# Mixer_NEXT_GEN_V3_2026-02-06.net
KiCad netlist of a schematic drawn in EasyEDA Pro
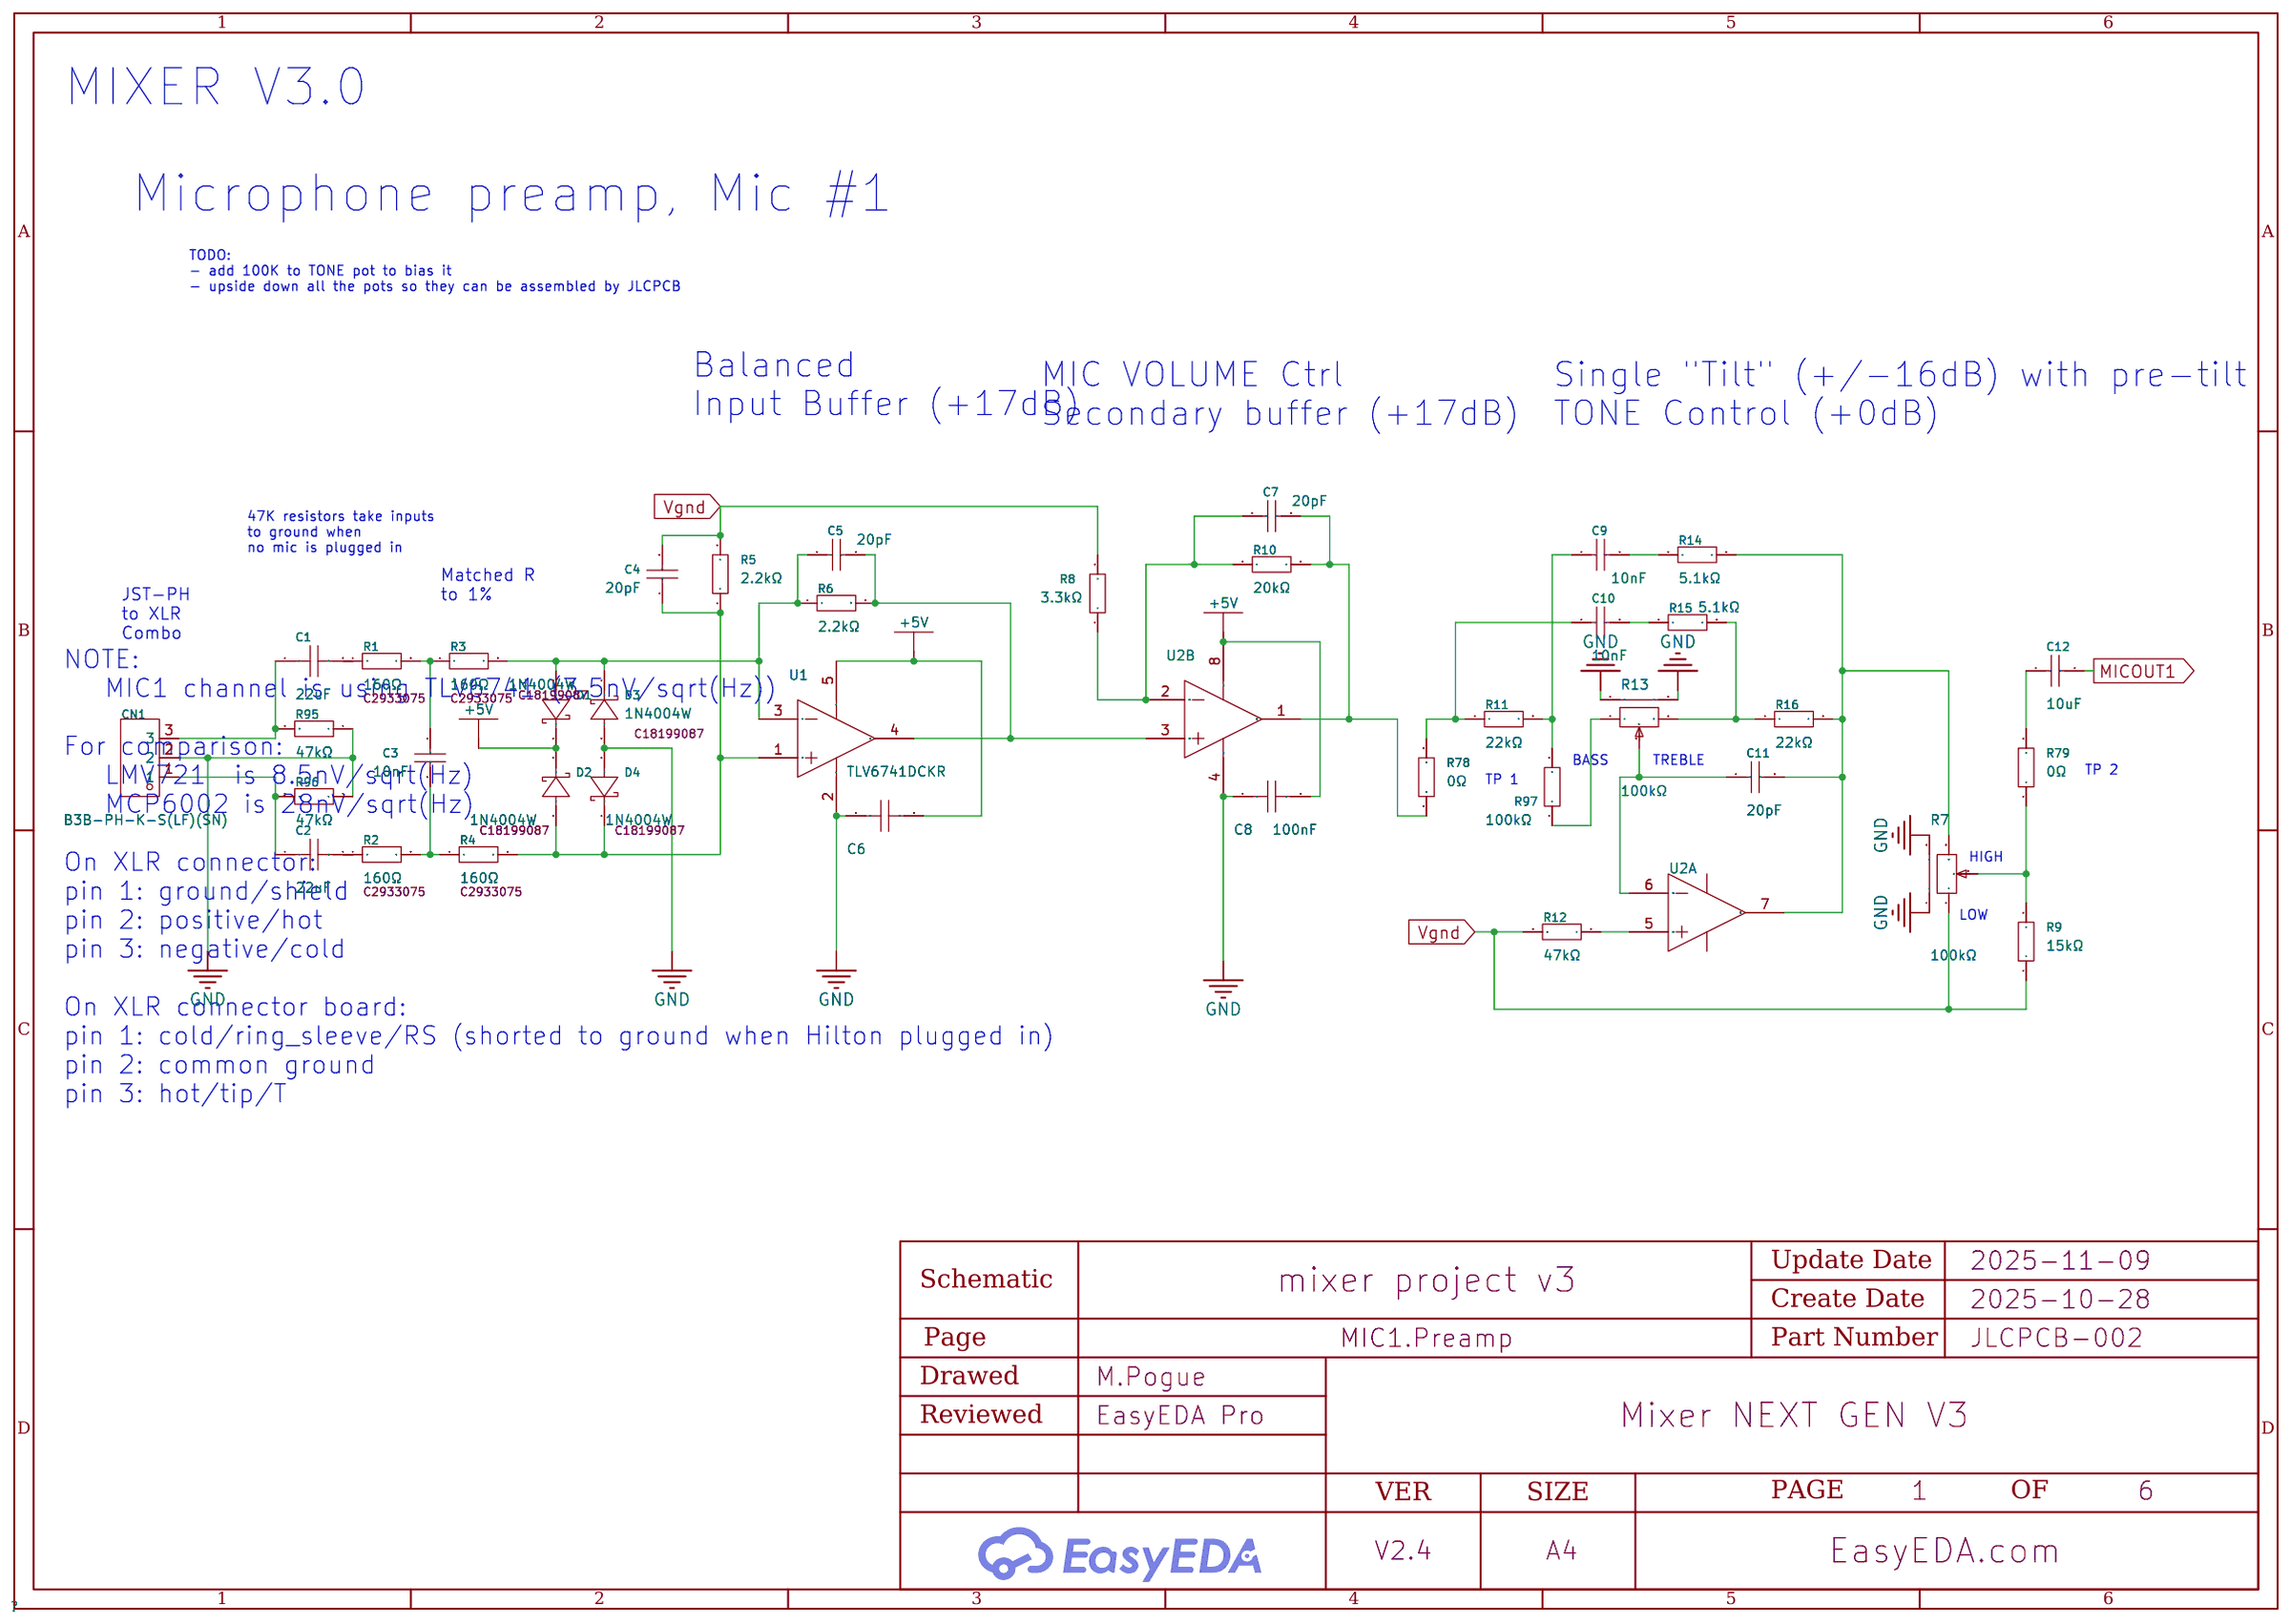
[diagram p0: MIC1.Preamp]
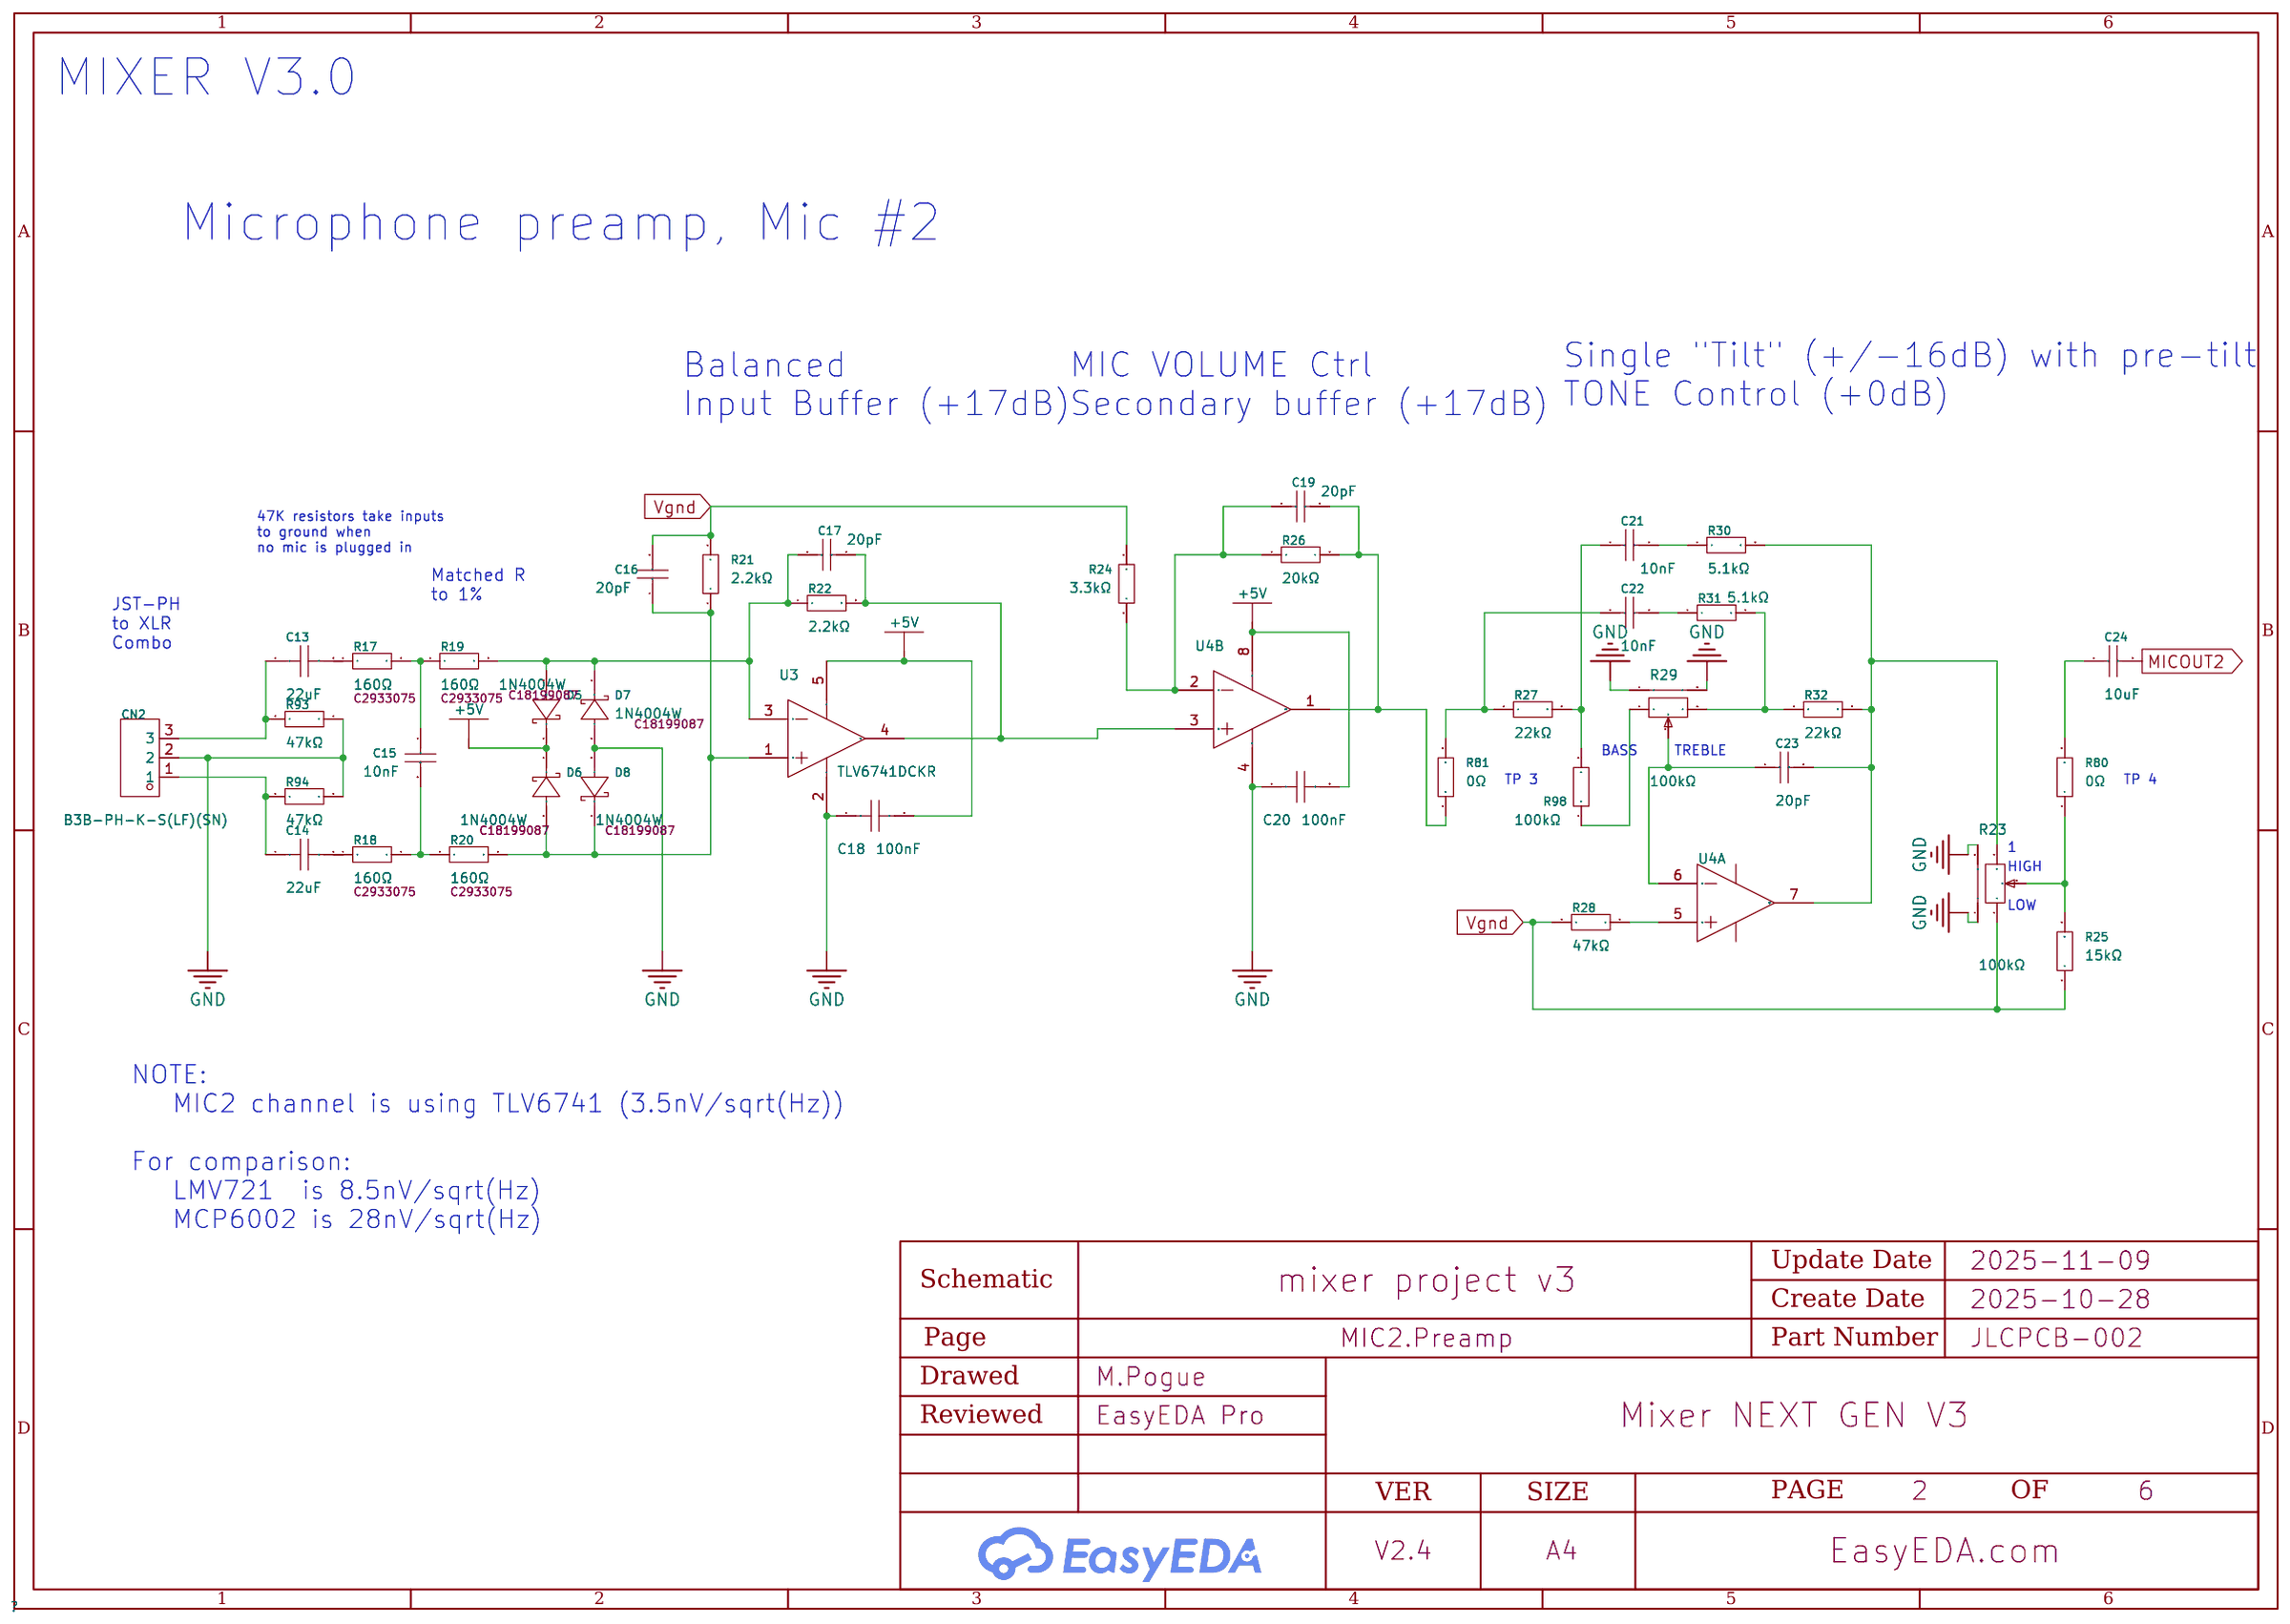
[diagram p1: MIC2.Preamp]
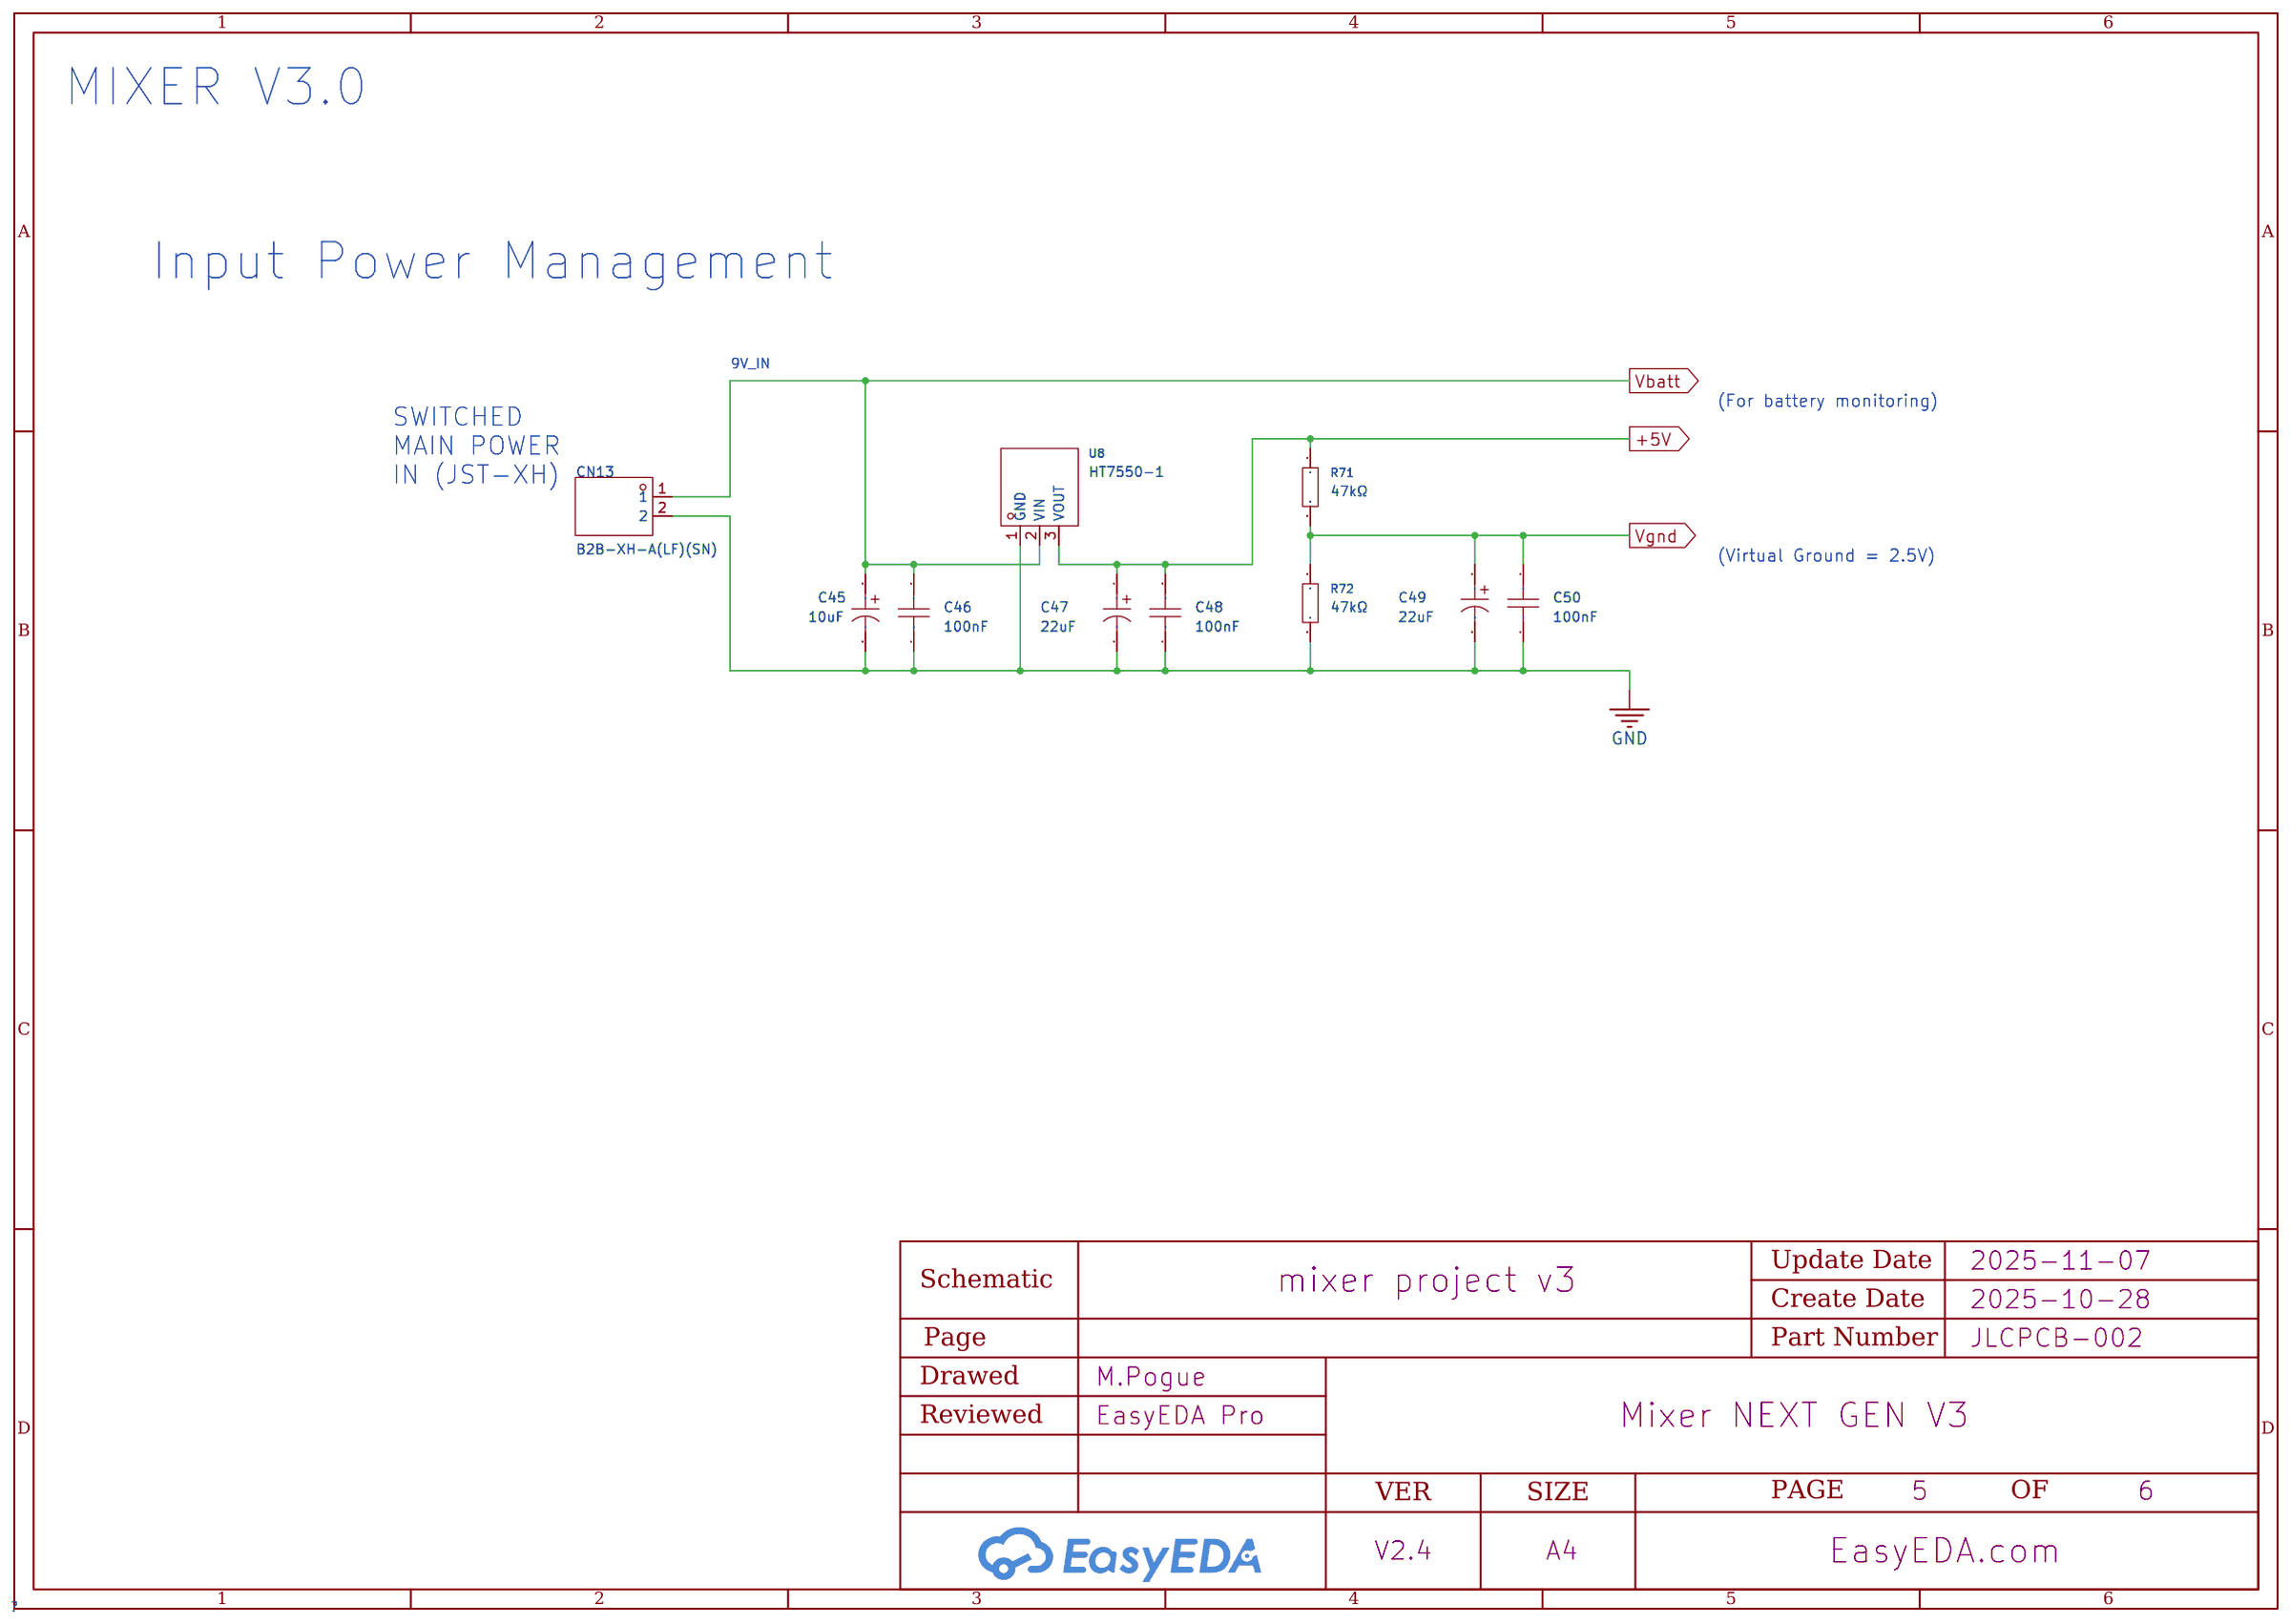
[diagram p2: PowerSupply]
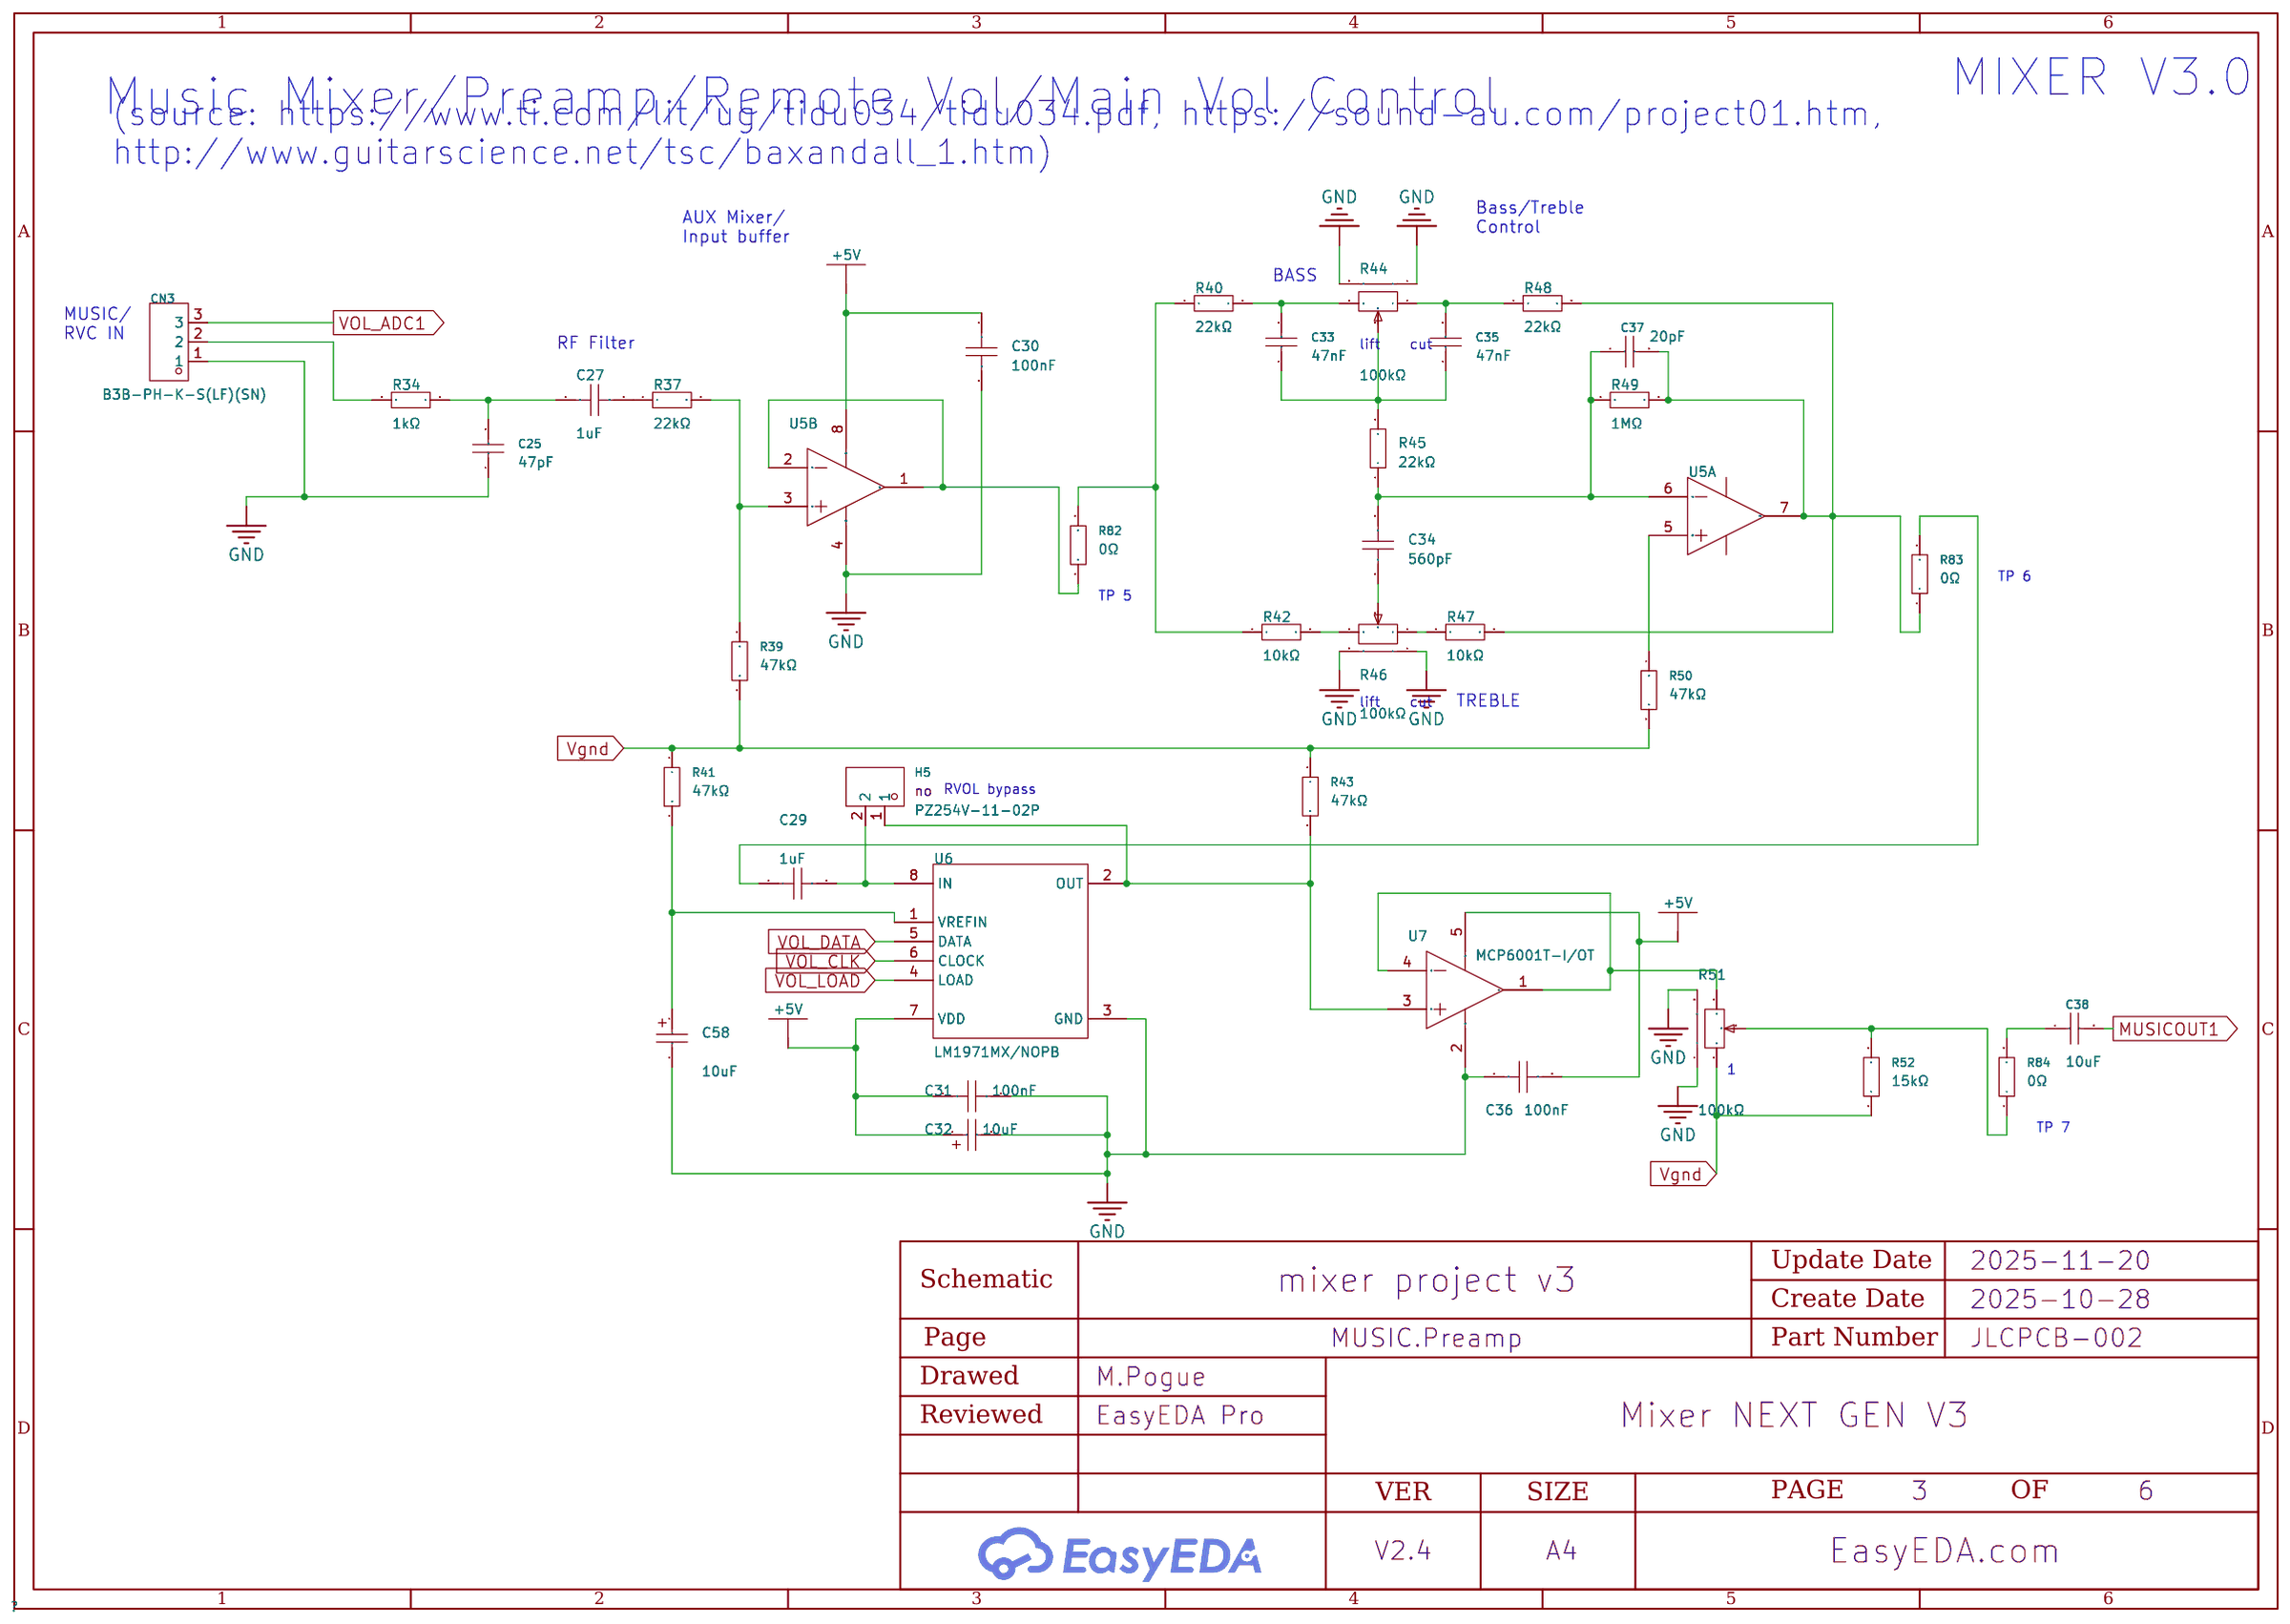
[diagram p3: MUSIC.Preamp]
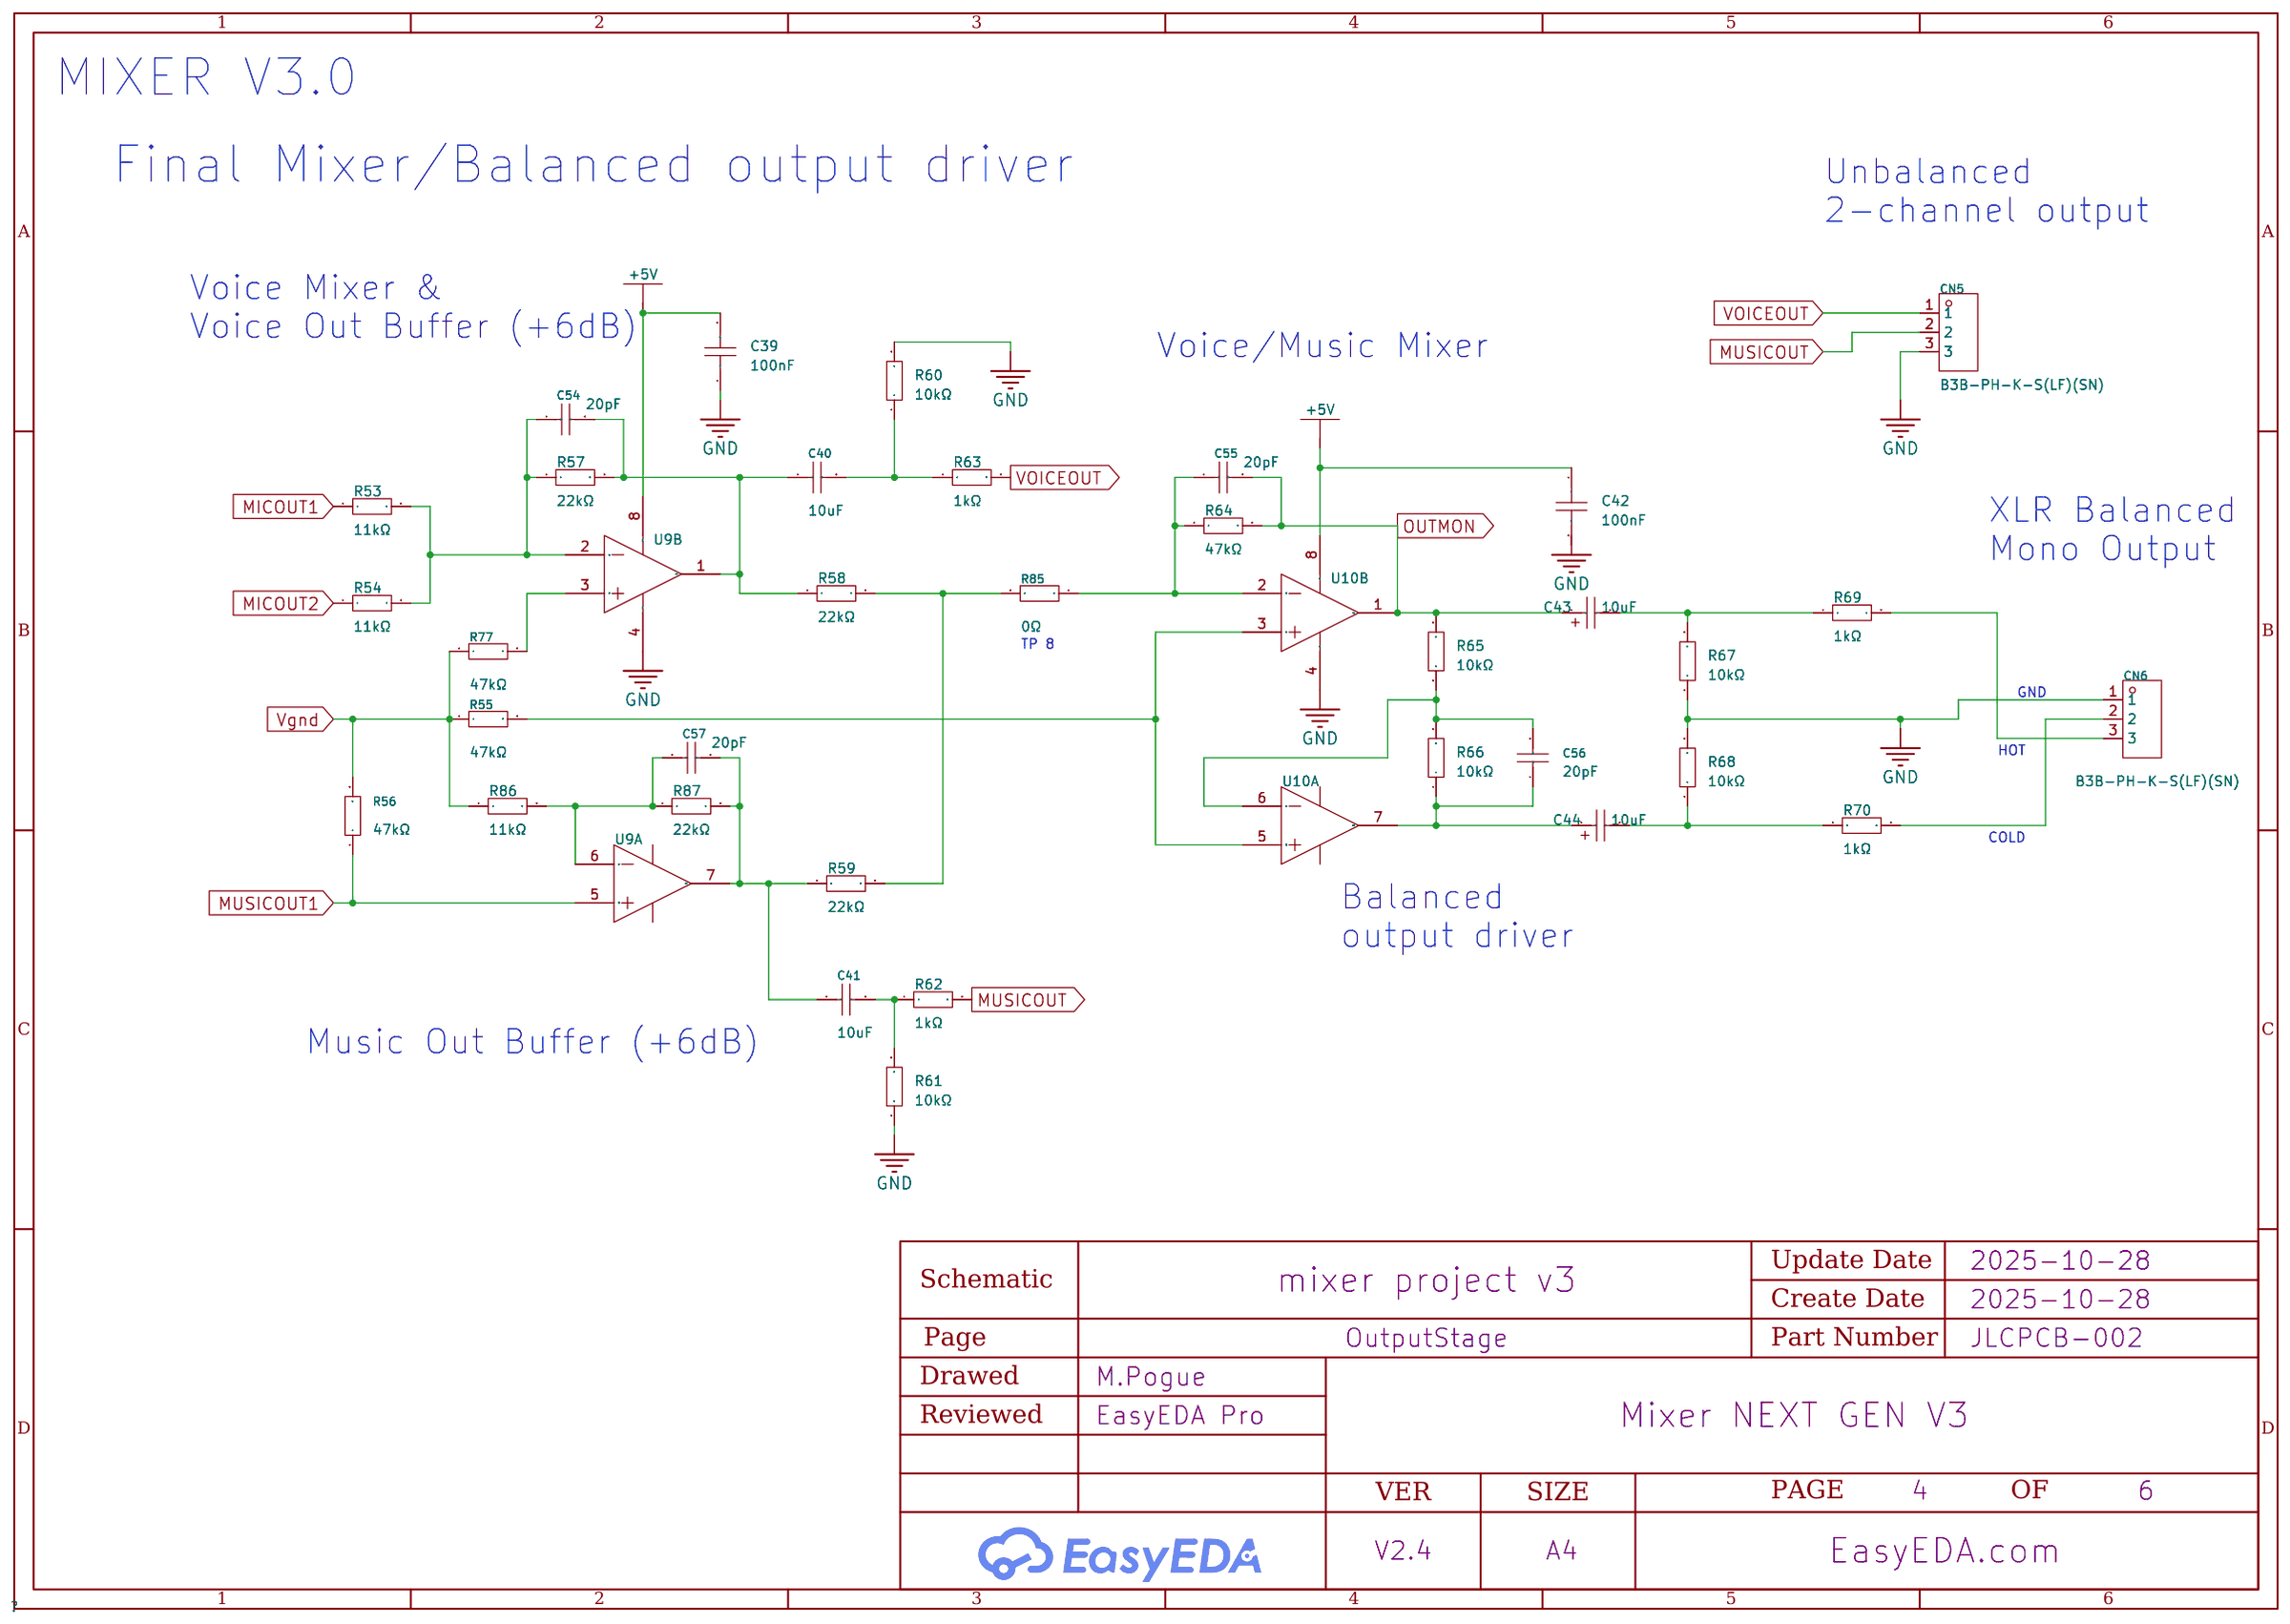
[diagram p4: OutputStage]
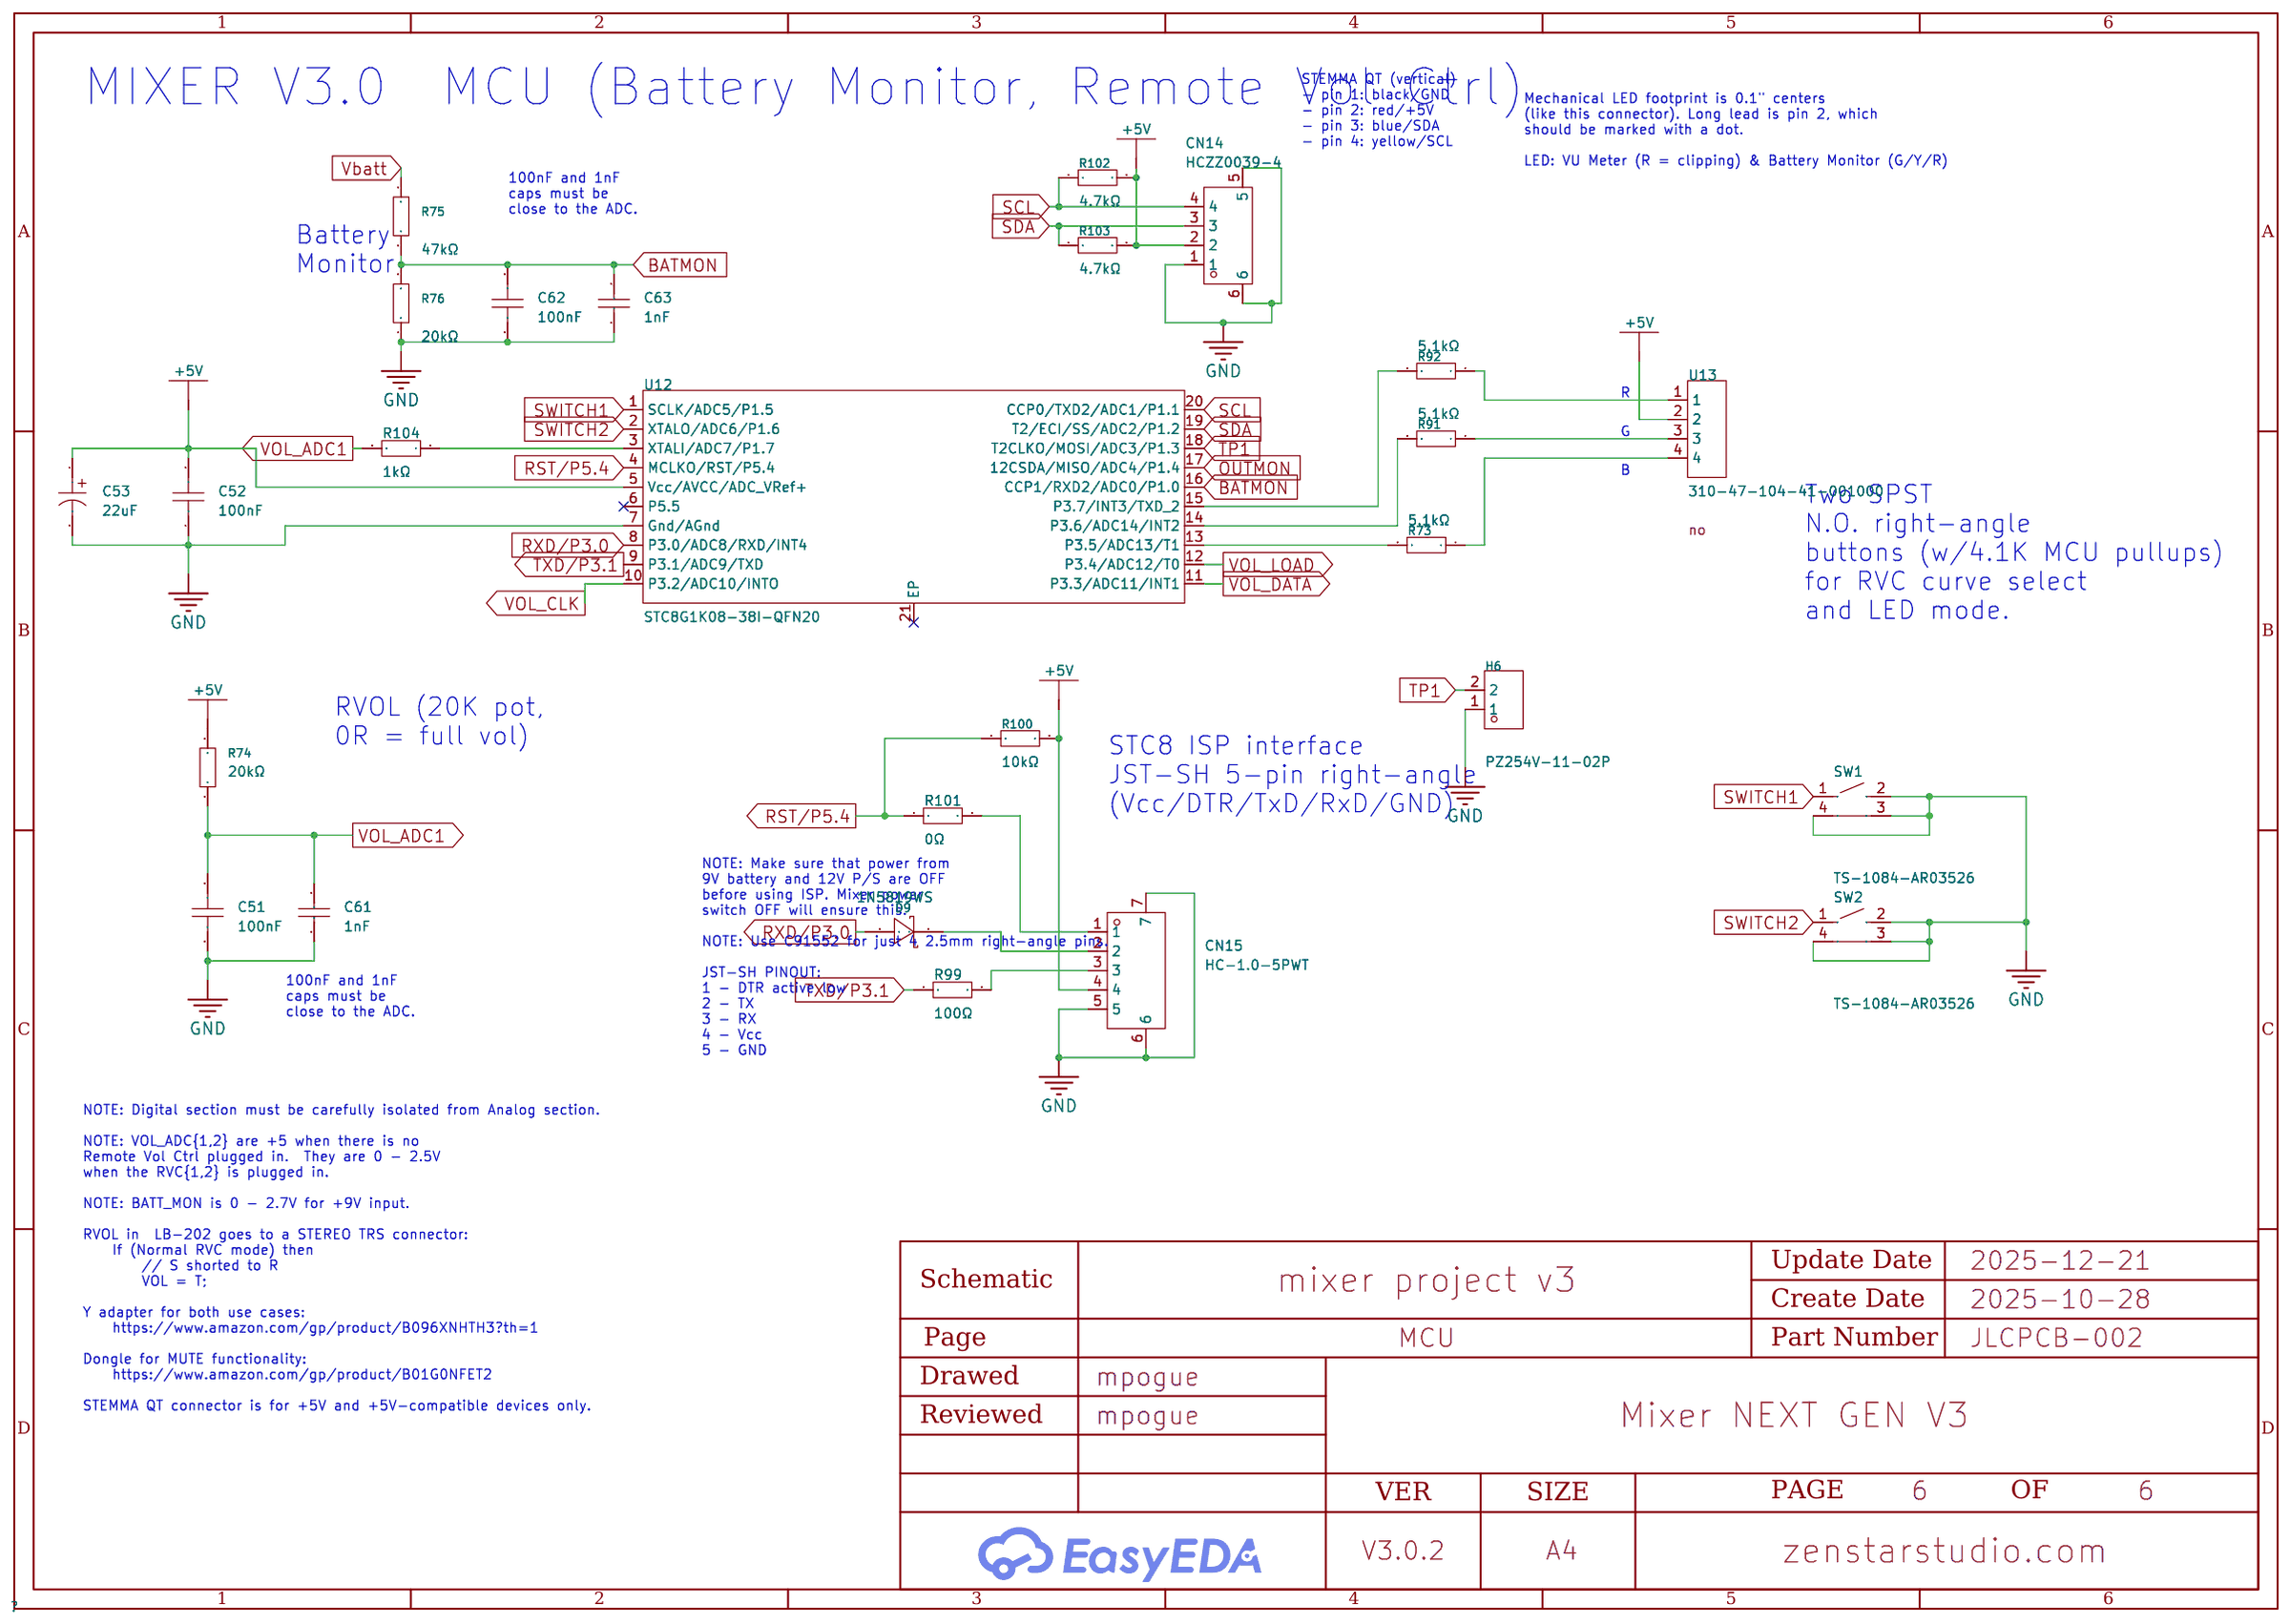
[diagram p5: MCU]

(export (version "E")
  (design (tool "Eeschema 10.0.6"))
  (components
    (comp (ref "C1")
      (value "22uF")
      (footprint "easyedapro:C0805")
      (fields
        (field (name "Manufacturer Part") "CL21A226MAQNNNE")
        (field (name "Manufacturer") "SAMSUNG(三星)")
      )
      (libsource (lib "easyedapro") (part "CL21A226MAQNNNE"))
    )
    (comp (ref "C2")
      (value "22uF")
      (footprint "easyedapro:C0805")
      (fields
        (field (name "Manufacturer Part") "CL21A226MAQNNNE")
        (field (name "Manufacturer") "SAMSUNG(三星)")
      )
      (libsource (lib "easyedapro") (part "CL21A226MAQNNNE"))
    )
    (comp (ref "C3")
      (value "10nF")
      (footprint "easyedapro:C0402")
      (fields
        (field (name "Manufacturer Part") "CL05B103KB5NNNC")
        (field (name "Manufacturer") "SAMSUNG(三星)")
      )
      (libsource (lib "easyedapro") (part "CL05B103KB5NNNC"))
    )
    (comp (ref "C4")
      (value "20pF")
      (footprint "easyedapro:C0402")
      (fields (field (name "Manufacturer Part") "0402CG200J500NT") (field (name "Manufacturer") "FH(风华)"))
      (libsource (lib "easyedapro") (part "0402CG200J500NT"))
    )
    (comp (ref "C5")
      (value "20pF")
      (footprint "easyedapro:C0402")
      (fields (field (name "Manufacturer Part") "0402CG200J500NT") (field (name "Manufacturer") "FH(风华)"))
      (libsource (lib "easyedapro") (part "0402CG200J500NT"))
    )
    (comp (ref "C6")
      (value "100nF")
      (fields
        (field (name "Manufacturer Part") "CL05B104KO5NNNC")
        (field (name "Manufacturer") "SAMSUNG(三星)")
      )
      (libsource (lib "easyedapro") (part "CAP"))
    )
    (comp (ref "C7")
      (value "20pF")
      (footprint "easyedapro:C0402")
      (fields (field (name "Manufacturer Part") "0402CG200J500NT") (field (name "Manufacturer") "FH(风华)"))
      (libsource (lib "easyedapro") (part "0402CG200J500NT"))
    )
    (comp (ref "C8")
      (value "100nF")
      (fields
        (field (name "Manufacturer Part") "CL05B104KO5NNNC")
        (field (name "Manufacturer") "SAMSUNG(三星)")
      )
      (libsource (lib "easyedapro") (part "CAP"))
    )
    (comp (ref "C9")
      (value "10nF")
      (fields
        (field (name "Manufacturer Part") "CL05B103KB5NNNC")
        (field (name "Manufacturer") "SAMSUNG(三星)")
      )
      (libsource (lib "easyedapro") (part "0402B472K500NT"))
    )
    (comp (ref "C10")
      (value "10nF")
      (fields
        (field (name "Manufacturer Part") "CL05B103KB5NNNC")
        (field (name "Manufacturer") "SAMSUNG(三星)")
      )
      (libsource (lib "easyedapro") (part "0402B472K500NT"))
    )
    (comp (ref "C11")
      (value "20pF")
      (footprint "easyedapro:C0402")
      (fields (field (name "Manufacturer Part") "0402CG200J500NT") (field (name "Manufacturer") "FH(风华)"))
      (libsource (lib "easyedapro") (part "0402CG200J500NT"))
    )
    (comp (ref "C12")
      (value "10uF")
      (footprint "easyedapro:C1206")
      (fields
        (field (name "Manufacturer Part") "CL31A106KBHNNNE")
        (field (name "Manufacturer") "SAMSUNG(三星)")
      )
      (libsource (lib "easyedapro") (part "CL31A106KBHNNNE"))
    )
    (comp (ref "CN1")
      (value "B3B-PH-K-S(LF)(SN)")
      (footprint "easyedapro:CONN-TH_B3B-PH-K-S")
      (fields (field (name "Manufacturer") "JST"))
      (libsource (lib "easyedapro") (part "B3B-PH-K-S(LF)(SN)"))
    )
    (comp (ref "D1")
      (value "1N4004W")
      (footprint "easyedapro:SOD-123FL_L2.7-W1.8-LS3.8-RD")
      (fields (field (name "Manufacturer") "R+O(宏嘉诚)") (field (name "Supplier Part") "C18199087"))
      (libsource (lib "easyedapro") (part "1N4004W_C18199087"))
    )
    (comp (ref "D2")
      (value "1N4004W")
      (footprint "easyedapro:SOD-123FL_L2.7-W1.8-LS3.8-RD")
      (fields (field (name "Manufacturer") "R+O(宏嘉诚)") (field (name "Supplier Part") "C18199087"))
      (libsource (lib "easyedapro") (part "1N4004W_C18199087"))
    )
    (comp (ref "D3")
      (value "1N4004W")
      (footprint "easyedapro:SOD-123FL_L2.7-W1.8-LS3.8-RD")
      (fields (field (name "Manufacturer") "R+O(宏嘉诚)") (field (name "Supplier Part") "C18199087"))
      (libsource (lib "easyedapro") (part "1N4004W_C18199087"))
    )
    (comp (ref "D4")
      (value "1N4004W")
      (footprint "easyedapro:SOD-123FL_L2.7-W1.8-LS3.8-RD")
      (fields (field (name "Manufacturer") "R+O(宏嘉诚)") (field (name "Supplier Part") "C18199087"))
      (libsource (lib "easyedapro") (part "1N4004W_C18199087"))
    )
    (comp (ref "R1")
      (value "160Ω")
      (footprint "easyedapro:R0402")
      (fields
        (field (name "Manufacturer Part") "FRC0402F1600TS")
        (field (name "Manufacturer") "FOJAN(富捷)")
        (field (name "Supplier Part") "C2933075")
      )
      (libsource (lib "easyedapro") (part "RC-02W1600FT"))
    )
    (comp (ref "R2")
      (value "160Ω")
      (footprint "easyedapro:R0402")
      (fields
        (field (name "Manufacturer Part") "FRC0402F1600TS")
        (field (name "Manufacturer") "FOJAN(富捷)")
        (field (name "Supplier Part") "C2933075")
      )
      (libsource (lib "easyedapro") (part "RC-02W1600FT"))
    )
    (comp (ref "R3")
      (value "160Ω")
      (footprint "easyedapro:R0402")
      (fields
        (field (name "Manufacturer Part") "FRC0402F1600TS")
        (field (name "Manufacturer") "FOJAN(富捷)")
        (field (name "Supplier Part") "C2933075")
      )
      (libsource (lib "easyedapro") (part "RC-02W1600FT"))
    )
    (comp (ref "R4")
      (value "160Ω")
      (footprint "easyedapro:R0402")
      (fields
        (field (name "Manufacturer Part") "FRC0402F1600TS")
        (field (name "Manufacturer") "FOJAN(富捷)")
        (field (name "Supplier Part") "C2933075")
      )
      (libsource (lib "easyedapro") (part "RC-02W1600FT"))
    )
    (comp (ref "R5")
      (value "2.2kΩ")
      (footprint "easyedapro:R0402")
      (fields
        (field (name "Manufacturer Part") "0402WGF2201TCE")
        (field (name "Manufacturer") "UNI-ROYAL(厚声)")
      )
      (libsource (lib "easyedapro") (part "0402WGF2201TCE"))
    )
    (comp (ref "R6")
      (value "2.2kΩ")
      (footprint "easyedapro:R0402")
      (fields
        (field (name "Manufacturer Part") "0402WGF2201TCE")
        (field (name "Manufacturer") "UNI-ROYAL(厚声)")
      )
      (libsource (lib "easyedapro") (part "0402WGF2201TCE"))
    )
    (comp (ref "R7")
      (value "100kΩ")
      (footprint "easyedapro:RES-ADJ-TH_RK09K1130AJ3")
      (description "Resistance: Tolerance:±20% Tolerance:±20% Power(Watts):50mW Turns:- Rated Voltage:20V")
      (fields
        (field (name "Manufacturer Part") "RK09K1130AU2")
        (field (name "Manufacturer") "ALPSALPINE(阿尔卑斯阿尔派)")
      )
      (libsource (lib "easyedapro") (part "RK09K1130AU2"))
    )
    (comp (ref "R8")
      (value "3.3kΩ")
      (footprint "easyedapro:R0402")
      (fields
        (field (name "Manufacturer Part") "0402WGF3301TCE")
        (field (name "Manufacturer") "UNI-ROYAL(厚声)")
      )
      (libsource (lib "easyedapro") (part "0402WGF3301TCE"))
    )
    (comp (ref "R9")
      (value "15kΩ")
      (footprint "easyedapro:R0402")
      (fields
        (field (name "Manufacturer Part") "0402WGF1502TCE")
        (field (name "Manufacturer") "UNI-ROYAL(厚声)")
      )
      (libsource (lib "easyedapro") (part "0402WGF1502TCE"))
    )
    (comp (ref "R10")
      (value "20kΩ")
      (footprint "easyedapro:R0402")
      (fields
        (field (name "Manufacturer Part") "0402WGF2002TCE")
        (field (name "Manufacturer") "UNI-ROYAL(厚声)")
      )
      (libsource (lib "easyedapro") (part "0402WGF2002TCE"))
    )
    (comp (ref "R11")
      (value "22kΩ")
      (footprint "easyedapro:R0402")
      (fields
        (field (name "Manufacturer Part") "0402WGF2202TCE")
        (field (name "Manufacturer") "UNI-ROYAL(厚声)")
      )
      (libsource (lib "easyedapro") (part "0402WGF2202TCE"))
    )
    (comp (ref "R12")
      (value "47kΩ")
      (footprint "easyedapro:R0402")
      (fields
        (field (name "Manufacturer Part") "0402WGF4702TCE")
        (field (name "Manufacturer") "UNI-ROYAL(厚声)")
      )
      (libsource (lib "easyedapro") (part "0402WGF4702TCE"))
    )
    (comp (ref "R13")
      (value "100kΩ")
      (footprint "easyedapro:RES-ADJ-TH_RK09K1130AJ3")
      (description "Resistance: Tolerance:±20% Tolerance:±20% Power(Watts):50mW Turns:- Rated Voltage:20V")
      (fields
        (field (name "Manufacturer Part") "RK09K1130AU2")
        (field (name "Manufacturer") "ALPSALPINE(阿尔卑斯阿尔派)")
      )
      (libsource (lib "easyedapro") (part "RK09K1130AU2"))
    )
    (comp (ref "R14")
      (value "5.1kΩ")
      (footprint "easyedapro:R0402")
      (fields
        (field (name "Manufacturer Part") "0402WGF5101TCE")
        (field (name "Manufacturer") "UNI-ROYAL(厚声)")
      )
      (libsource (lib "easyedapro") (part "0402WGF5101TCE"))
    )
    (comp (ref "R15")
      (value "5.1kΩ")
      (footprint "easyedapro:R0402")
      (fields
        (field (name "Manufacturer Part") "0402WGF5101TCE")
        (field (name "Manufacturer") "UNI-ROYAL(厚声)")
      )
      (libsource (lib "easyedapro") (part "0402WGF5101TCE"))
    )
    (comp (ref "R16")
      (value "22kΩ")
      (footprint "easyedapro:R0402")
      (fields
        (field (name "Manufacturer Part") "0402WGF2202TCE")
        (field (name "Manufacturer") "UNI-ROYAL(厚声)")
      )
      (libsource (lib "easyedapro") (part "0402WGF2202TCE"))
    )
    (comp (ref "R78")
      (value "0Ω")
      (footprint "easyedapro:R0805")
      (fields
        (field (name "Manufacturer Part") "0805W8F0000T5E")
        (field (name "Manufacturer") "UNI-ROYAL(厚声)")
      )
      (libsource (lib "easyedapro") (part "0805W8F0000T5E"))
    )
    (comp (ref "R79")
      (value "0Ω")
      (footprint "easyedapro:R0805")
      (fields
        (field (name "Manufacturer Part") "0805W8F0000T5E")
        (field (name "Manufacturer") "UNI-ROYAL(厚声)")
      )
      (libsource (lib "easyedapro") (part "0805W8F0000T5E"))
    )
    (comp (ref "R95")
      (value "47kΩ")
      (footprint "easyedapro:R0402")
      (fields
        (field (name "Manufacturer Part") "0402WGF4702TCE")
        (field (name "Manufacturer") "UNI-ROYAL(厚声)")
      )
      (libsource (lib "easyedapro") (part "0402WGF4702TCE"))
    )
    (comp (ref "R96")
      (value "47kΩ")
      (footprint "easyedapro:R0402")
      (fields
        (field (name "Manufacturer Part") "0402WGF4702TCE")
        (field (name "Manufacturer") "UNI-ROYAL(厚声)")
      )
      (libsource (lib "easyedapro") (part "0402WGF4702TCE"))
    )
    (comp (ref "R97")
      (value "100kΩ")
      (footprint "easyedapro:R0402")
      (fields
        (field (name "Manufacturer Part") "0402WGF1003TCE")
        (field (name "Manufacturer") "UNI-ROYAL(厚声)")
      )
      (libsource (lib "easyedapro") (part "0402WGF1003TCE"))
    )
    (comp (ref "U1")
      (value "TLV6741DCKR")
      (footprint "easyedapro:SC-70-5_L2.0-W1.3-P0.65-LS2.1-BR")
      (fields (field (name "Manufacturer") "TI(德州仪器)"))
      (libsource (lib "easyedapro") (part "TLV6741DCKR"))
    )
    (comp (ref "U2")
      (value "MCP6002-I/SN")
      (footprint "easyedapro:SOIC-8_L4.9-W3.9-P1.27-LS6.0-BL")
      (fields (field (name "Manufacturer") "MICROCHIP(美国微芯)"))
      (libsource (lib "easyedapro") (part "MCP6002-I/SN"))
    )
    (comp (ref "C13")
      (value "22uF")
      (footprint "easyedapro:C0805")
      (fields
        (field (name "Manufacturer Part") "CL21A226MAQNNNE")
        (field (name "Manufacturer") "SAMSUNG(三星)")
      )
      (libsource (lib "easyedapro") (part "CL21A226MAQNNNE"))
    )
    (comp (ref "C14")
      (value "22uF")
      (footprint "easyedapro:C0805")
      (fields
        (field (name "Manufacturer Part") "CL21A226MAQNNNE")
        (field (name "Manufacturer") "SAMSUNG(三星)")
      )
      (libsource (lib "easyedapro") (part "CL21A226MAQNNNE"))
    )
    (comp (ref "C15")
      (value "10nF")
      (footprint "easyedapro:C0402")
      (fields
        (field (name "Manufacturer Part") "CL05B103KB5NNNC")
        (field (name "Manufacturer") "SAMSUNG(三星)")
      )
      (libsource (lib "easyedapro") (part "CL05B103KB5NNNC"))
    )
    (comp (ref "C16")
      (value "20pF")
      (footprint "easyedapro:C0402")
      (fields (field (name "Manufacturer Part") "0402CG200J500NT") (field (name "Manufacturer") "FH(风华)"))
      (libsource (lib "easyedapro") (part "0402CG200J500NT"))
    )
    (comp (ref "C17")
      (value "20pF")
      (footprint "easyedapro:C0402")
      (fields (field (name "Manufacturer Part") "0402CG200J500NT") (field (name "Manufacturer") "FH(风华)"))
      (libsource (lib "easyedapro") (part "0402CG200J500NT"))
    )
    (comp (ref "C18")
      (value "100nF")
      (fields
        (field (name "Manufacturer Part") "CL05B104KO5NNNC")
        (field (name "Manufacturer") "SAMSUNG(三星)")
      )
      (libsource (lib "easyedapro") (part "CAP"))
    )
    (comp (ref "C19")
      (value "20pF")
      (footprint "easyedapro:C0402")
      (fields (field (name "Manufacturer Part") "0402CG200J500NT") (field (name "Manufacturer") "FH(风华)"))
      (libsource (lib "easyedapro") (part "0402CG200J500NT"))
    )
    (comp (ref "C20")
      (value "100nF")
      (fields
        (field (name "Manufacturer Part") "CL05B104KO5NNNC")
        (field (name "Manufacturer") "SAMSUNG(三星)")
      )
      (libsource (lib "easyedapro") (part "CAP"))
    )
    (comp (ref "C21")
      (value "10nF")
      (fields
        (field (name "Manufacturer Part") "CL05B103KB5NNNC")
        (field (name "Manufacturer") "SAMSUNG(三星)")
      )
      (libsource (lib "easyedapro") (part "0402B472K500NT"))
    )
    (comp (ref "C22")
      (value "10nF")
      (fields
        (field (name "Manufacturer Part") "CL05B103KB5NNNC")
        (field (name "Manufacturer") "SAMSUNG(三星)")
      )
      (libsource (lib "easyedapro") (part "0402B472K500NT"))
    )
    (comp (ref "C23")
      (value "20pF")
      (footprint "easyedapro:C0402")
      (fields (field (name "Manufacturer Part") "0402CG200J500NT") (field (name "Manufacturer") "FH(风华)"))
      (libsource (lib "easyedapro") (part "0402CG200J500NT"))
    )
    (comp (ref "C24")
      (value "10uF")
      (footprint "easyedapro:C1206")
      (fields
        (field (name "Manufacturer Part") "CL31A106KBHNNNE")
        (field (name "Manufacturer") "SAMSUNG(三星)")
      )
      (libsource (lib "easyedapro") (part "CL31A106KBHNNNE"))
    )
    (comp (ref "CN2")
      (value "B3B-PH-K-S(LF)(SN)")
      (footprint "easyedapro:CONN-TH_B3B-PH-K-S")
      (fields (field (name "Manufacturer") "JST"))
      (libsource (lib "easyedapro") (part "B3B-PH-K-S(LF)(SN)"))
    )
    (comp (ref "D5")
      (value "1N4004W")
      (footprint "easyedapro:SOD-123FL_L2.7-W1.8-LS3.8-RD")
      (fields (field (name "Manufacturer") "R+O(宏嘉诚)") (field (name "Supplier Part") "C18199087"))
      (libsource (lib "easyedapro") (part "1N4004W_C18199087"))
    )
    (comp (ref "D6")
      (value "1N4004W")
      (footprint "easyedapro:SOD-123FL_L2.7-W1.8-LS3.8-RD")
      (fields (field (name "Manufacturer") "R+O(宏嘉诚)") (field (name "Supplier Part") "C18199087"))
      (libsource (lib "easyedapro") (part "1N4004W_C18199087"))
    )
    (comp (ref "D7")
      (value "1N4004W")
      (footprint "easyedapro:SOD-123FL_L2.7-W1.8-LS3.8-RD")
      (fields (field (name "Manufacturer") "R+O(宏嘉诚)") (field (name "Supplier Part") "C18199087"))
      (libsource (lib "easyedapro") (part "1N4004W_C18199087"))
    )
    (comp (ref "D8")
      (value "1N4004W")
      (footprint "easyedapro:SOD-123FL_L2.7-W1.8-LS3.8-RD")
      (fields (field (name "Manufacturer") "R+O(宏嘉诚)") (field (name "Supplier Part") "C18199087"))
      (libsource (lib "easyedapro") (part "1N4004W_C18199087"))
    )
    (comp (ref "R17")
      (value "160Ω")
      (footprint "easyedapro:R0402")
      (fields
        (field (name "Manufacturer Part") "FRC0402F1600TS")
        (field (name "Manufacturer") "FOJAN(富捷)")
        (field (name "Supplier Part") "C2933075")
      )
      (libsource (lib "easyedapro") (part "RC-02W1600FT"))
    )
    (comp (ref "R18")
      (value "160Ω")
      (footprint "easyedapro:R0402")
      (fields
        (field (name "Manufacturer Part") "FRC0402F1600TS")
        (field (name "Manufacturer") "FOJAN(富捷)")
        (field (name "Supplier Part") "C2933075")
      )
      (libsource (lib "easyedapro") (part "RC-02W1600FT"))
    )
    (comp (ref "R19")
      (value "160Ω")
      (footprint "easyedapro:R0402")
      (fields
        (field (name "Manufacturer Part") "FRC0402F1600TS")
        (field (name "Manufacturer") "FOJAN(富捷)")
        (field (name "Supplier Part") "C2933075")
      )
      (libsource (lib "easyedapro") (part "RC-02W1600FT"))
    )
    (comp (ref "R20")
      (value "160Ω")
      (footprint "easyedapro:R0402")
      (fields
        (field (name "Manufacturer Part") "FRC0402F1600TS")
        (field (name "Manufacturer") "FOJAN(富捷)")
        (field (name "Supplier Part") "C2933075")
      )
      (libsource (lib "easyedapro") (part "RC-02W1600FT"))
    )
    (comp (ref "R21")
      (value "2.2kΩ")
      (footprint "easyedapro:R0402")
      (fields
        (field (name "Manufacturer Part") "0402WGF2201TCE")
        (field (name "Manufacturer") "UNI-ROYAL(厚声)")
      )
      (libsource (lib "easyedapro") (part "0402WGF2201TCE"))
    )
    (comp (ref "R22")
      (value "2.2kΩ")
      (footprint "easyedapro:R0402")
      (fields
        (field (name "Manufacturer Part") "0402WGF2201TCE")
        (field (name "Manufacturer") "UNI-ROYAL(厚声)")
      )
      (libsource (lib "easyedapro") (part "0402WGF2201TCE"))
    )
    (comp (ref "R23")
      (value "100kΩ")
      (footprint "easyedapro:RES-ADJ-TH_RK09K1130AJ3")
      (description "Resistance: Tolerance:±20% Tolerance:±20% Power(Watts):50mW Turns:- Rated Voltage:20V")
      (fields
        (field (name "Manufacturer Part") "RK09K1130AU2")
        (field (name "Manufacturer") "ALPSALPINE(阿尔卑斯阿尔派)")
      )
      (libsource (lib "easyedapro") (part "RK09K1130AU2"))
    )
    (comp (ref "R24")
      (value "3.3kΩ")
      (footprint "easyedapro:R0402")
      (fields
        (field (name "Manufacturer Part") "0402WGF3301TCE")
        (field (name "Manufacturer") "UNI-ROYAL(厚声)")
      )
      (libsource (lib "easyedapro") (part "0402WGF3301TCE"))
    )
    (comp (ref "R25")
      (value "15kΩ")
      (footprint "easyedapro:R0402")
      (fields
        (field (name "Manufacturer Part") "0402WGF1502TCE")
        (field (name "Manufacturer") "UNI-ROYAL(厚声)")
      )
      (libsource (lib "easyedapro") (part "0402WGF1502TCE"))
    )
    (comp (ref "R26")
      (value "20kΩ")
      (footprint "easyedapro:R0402")
      (fields
        (field (name "Manufacturer Part") "0402WGF2002TCE")
        (field (name "Manufacturer") "UNI-ROYAL(厚声)")
      )
      (libsource (lib "easyedapro") (part "0402WGF2002TCE"))
    )
    (comp (ref "R27")
      (value "22kΩ")
      (footprint "easyedapro:R0402")
      (fields
        (field (name "Manufacturer Part") "0402WGF2202TCE")
        (field (name "Manufacturer") "UNI-ROYAL(厚声)")
      )
      (libsource (lib "easyedapro") (part "0402WGF2202TCE"))
    )
    (comp (ref "R28")
      (value "47kΩ")
      (footprint "easyedapro:R0402")
      (fields
        (field (name "Manufacturer Part") "0402WGF4702TCE")
        (field (name "Manufacturer") "UNI-ROYAL(厚声)")
      )
      (libsource (lib "easyedapro") (part "0402WGF4702TCE"))
    )
    (comp (ref "R29")
      (value "100kΩ")
      (footprint "easyedapro:RES-ADJ-TH_RK09K1130AJ3")
      (description "Resistance: Tolerance:±20% Tolerance:±20% Power(Watts):50mW Turns:- Rated Voltage:20V")
      (fields
        (field (name "Manufacturer Part") "RK09K1130AU2")
        (field (name "Manufacturer") "ALPSALPINE(阿尔卑斯阿尔派)")
      )
      (libsource (lib "easyedapro") (part "RK09K1130AU2"))
    )
    (comp (ref "R30")
      (value "5.1kΩ")
      (footprint "easyedapro:R0402")
      (fields
        (field (name "Manufacturer Part") "0402WGF5101TCE")
        (field (name "Manufacturer") "UNI-ROYAL(厚声)")
      )
      (libsource (lib "easyedapro") (part "0402WGF5101TCE"))
    )
    (comp (ref "R31")
      (value "5.1kΩ")
      (footprint "easyedapro:R0402")
      (fields
        (field (name "Manufacturer Part") "0402WGF5101TCE")
        (field (name "Manufacturer") "UNI-ROYAL(厚声)")
      )
      (libsource (lib "easyedapro") (part "0402WGF5101TCE"))
    )
    (comp (ref "R32")
      (value "22kΩ")
      (footprint "easyedapro:R0402")
      (fields
        (field (name "Manufacturer Part") "0402WGF2202TCE")
        (field (name "Manufacturer") "UNI-ROYAL(厚声)")
      )
      (libsource (lib "easyedapro") (part "0402WGF2202TCE"))
    )
    (comp (ref "R80")
      (value "0Ω")
      (footprint "easyedapro:R0805")
      (fields
        (field (name "Manufacturer Part") "0805W8F0000T5E")
        (field (name "Manufacturer") "UNI-ROYAL(厚声)")
      )
      (libsource (lib "easyedapro") (part "0805W8F0000T5E"))
    )
    (comp (ref "R81")
      (value "0Ω")
      (footprint "easyedapro:R0805")
      (fields
        (field (name "Manufacturer Part") "0805W8F0000T5E")
        (field (name "Manufacturer") "UNI-ROYAL(厚声)")
      )
      (libsource (lib "easyedapro") (part "0805W8F0000T5E"))
    )
    (comp (ref "R93")
      (value "47kΩ")
      (footprint "easyedapro:R0402")
      (fields
        (field (name "Manufacturer Part") "0402WGF4702TCE")
        (field (name "Manufacturer") "UNI-ROYAL(厚声)")
      )
      (libsource (lib "easyedapro") (part "0402WGF4702TCE"))
    )
    (comp (ref "R94")
      (value "47kΩ")
      (footprint "easyedapro:R0402")
      (fields
        (field (name "Manufacturer Part") "0402WGF4702TCE")
        (field (name "Manufacturer") "UNI-ROYAL(厚声)")
      )
      (libsource (lib "easyedapro") (part "0402WGF4702TCE"))
    )
    (comp (ref "R98")
      (value "100kΩ")
      (footprint "easyedapro:R0402")
      (fields
        (field (name "Manufacturer Part") "0402WGF1003TCE")
        (field (name "Manufacturer") "UNI-ROYAL(厚声)")
      )
      (libsource (lib "easyedapro") (part "0402WGF1003TCE"))
    )
    (comp (ref "U3")
      (value "TLV6741DCKR")
      (footprint "easyedapro:SC-70-5_L2.0-W1.3-P0.65-LS2.1-BR")
      (fields (field (name "Manufacturer") "TI(德州仪器)"))
      (libsource (lib "easyedapro") (part "TLV6741DCKR"))
    )
    (comp (ref "U4")
      (value "MCP6002-I/SN")
      (footprint "easyedapro:SOIC-8_L4.9-W3.9-P1.27-LS6.0-BL")
      (fields (field (name "Manufacturer") "MICROCHIP(美国微芯)"))
      (libsource (lib "easyedapro") (part "MCP6002-I/SN"))
    )
    (comp (ref "C45")
      (value "10uF")
      (footprint "easyedapro:CAP-SMD_L3.2-W1.6")
      (fields
        (field (name "Manufacturer Part") "CA45-B-25V-10uF-K")
        (field (name "Manufacturer") "CEC(振华新云)")
      )
      (libsource (lib "easyedapro") (part "CA45-A-16V-22UF-K"))
    )
    (comp (ref "C46")
      (value "100nF")
      (fields
        (field (name "Manufacturer Part") "CL05B104KB54PNC")
        (field (name "Manufacturer") "SAMSUNG(三星)")
      )
      (libsource (lib "easyedapro") (part "CAP"))
    )
    (comp (ref "C47")
      (value "22uF")
      (footprint "easyedapro:CAP-SMD_L3.2-W1.6")
      (fields
        (field (name "Manufacturer Part") "CA45-A-16V-22uF-K")
        (field (name "Manufacturer") "CEC(振华新云)")
      )
      (libsource (lib "easyedapro") (part "CA45-A-16V-22UF-K"))
    )
    (comp (ref "C48")
      (value "100nF")
      (fields
        (field (name "Manufacturer Part") "CL05B104KO5NNNC")
        (field (name "Manufacturer") "SAMSUNG(三星)")
      )
      (libsource (lib "easyedapro") (part "CAP"))
    )
    (comp (ref "C49")
      (value "22uF")
      (footprint "easyedapro:CAP-SMD_L3.2-W1.6")
      (fields
        (field (name "Manufacturer Part") "CA45-A-16V-22uF-K")
        (field (name "Manufacturer") "CEC(振华新云)")
      )
      (libsource (lib "easyedapro") (part "CA45-A-16V-22UF-K"))
    )
    (comp (ref "C50")
      (value "100nF")
      (fields
        (field (name "Manufacturer Part") "CL05B104KO5NNNC")
        (field (name "Manufacturer") "SAMSUNG(三星)")
      )
      (libsource (lib "easyedapro") (part "CAP"))
    )
    (comp (ref "CN13")
      (value "B2B-XH-A(LF)(SN)")
      (footprint "easyedapro:CONN-TH_B2B-XH-A-LF-SN")
      (fields (field (name "Manufacturer") "JST"))
      (libsource (lib "easyedapro") (part "B2B-XH-A (LF)(SN)"))
    )
    (comp (ref "R71")
      (value "47kΩ")
      (footprint "easyedapro:R0402")
      (fields
        (field (name "Manufacturer Part") "0402WGF4702TCE")
        (field (name "Manufacturer") "UNI-ROYAL(厚声)")
      )
      (libsource (lib "easyedapro") (part "0402WGF4702TCE"))
    )
    (comp (ref "R72")
      (value "47kΩ")
      (footprint "easyedapro:R0402")
      (fields
        (field (name "Manufacturer Part") "0402WGF4702TCE")
        (field (name "Manufacturer") "UNI-ROYAL(厚声)")
      )
      (libsource (lib "easyedapro") (part "0402WGF4702TCE"))
    )
    (comp (ref "U8")
      (value "HT7550-1")
      (footprint "easyedapro:SOT-89_L4.5-W2.5-P1.50-LS4.2-BR")
      (fields (field (name "Manufacturer") "UMW(友台半导体)"))
      (libsource (lib "easyedapro") (part "HT7550-1_C347189"))
    )
    (comp (ref "C25")
      (value "47pF")
      (footprint "easyedapro:C0402")
      (fields (field (name "Manufacturer Part") "0402CG470J500NT") (field (name "Manufacturer") "FH(风华)"))
      (libsource (lib "easyedapro") (part "0402CG470J500NT"))
    )
    (comp (ref "C27")
      (value "1uF")
      (fields
        (field (name "Manufacturer Part") "CL05A105KA5NQNC")
        (field (name "Manufacturer") "SAMSUNG(三星)")
      )
      (libsource (lib "easyedapro") (part "CAP"))
    )
    (comp (ref "C29")
      (value "1uF")
      (fields
        (field (name "Manufacturer Part") "CL05A105KA5NQNC")
        (field (name "Manufacturer") "SAMSUNG(三星)")
      )
      (libsource (lib "easyedapro") (part "CAP"))
    )
    (comp (ref "C30")
      (value "100nF")
      (fields
        (field (name "Manufacturer Part") "CL05B104KO5NNNC")
        (field (name "Manufacturer") "SAMSUNG(三星)")
      )
      (libsource (lib "easyedapro") (part "CAP"))
    )
    (comp (ref "C31")
      (value "100nF")
      (fields
        (field (name "Manufacturer Part") "CL05B104KO5NNNC")
        (field (name "Manufacturer") "SAMSUNG(三星)")
      )
      (libsource (lib "easyedapro") (part "CAP"))
    )
    (comp (ref "C32")
      (value "10uF")
      (footprint "easyedapro:CAP-SMD_L3.2-W1.6-RD-C7171")
      (fields (field (name "Manufacturer Part") "TAJA106K016RNJ") (field (name "Manufacturer") "Kyocera AVX"))
      (libsource (lib "easyedapro") (part "TAJA106K016RNJ"))
    )
    (comp (ref "C33")
      (value "47nF")
      (footprint "easyedapro:C0603")
      (fields
        (field (name "Manufacturer Part") "CL10B473KB8NNNC")
        (field (name "Manufacturer") "SAMSUNG(三星)")
      )
      (libsource (lib "easyedapro") (part "CL10B473KB8NNNC"))
    )
    (comp (ref "C34")
      (value "560pF")
      (footprint "easyedapro:C0402")
      (fields
        (field (name "Manufacturer Part") "CC0402JRX7R9BB561")
        (field (name "Manufacturer") "YAGEO(国巨)")
      )
      (libsource (lib "easyedapro") (part "CC0402JRX7R9BB561"))
    )
    (comp (ref "C35")
      (value "47nF")
      (footprint "easyedapro:C0603")
      (fields
        (field (name "Manufacturer Part") "CL10B473KB8NNNC")
        (field (name "Manufacturer") "SAMSUNG(三星)")
      )
      (libsource (lib "easyedapro") (part "CL10B473KB8NNNC"))
    )
    (comp (ref "C36")
      (value "100nF")
      (fields
        (field (name "Manufacturer Part") "CL05B104KO5NNNC")
        (field (name "Manufacturer") "SAMSUNG(三星)")
      )
      (libsource (lib "easyedapro") (part "CAP"))
    )
    (comp (ref "C37")
      (value "20pF")
      (footprint "easyedapro:C0402")
      (fields (field (name "Manufacturer Part") "0402CG200J500NT") (field (name "Manufacturer") "FH(风华)"))
      (libsource (lib "easyedapro") (part "0402CG200J500NT"))
    )
    (comp (ref "C38")
      (value "10uF")
      (footprint "easyedapro:C1206")
      (fields
        (field (name "Manufacturer Part") "CL31A106KBHNNNE")
        (field (name "Manufacturer") "SAMSUNG(三星)")
      )
      (libsource (lib "easyedapro") (part "CL31A106KBHNNNE"))
    )
    (comp (ref "C58")
      (value "10uF")
      (footprint "easyedapro:CAP-SMD_L3.2-W1.6-RD-C7171")
      (fields (field (name "Manufacturer Part") "TAJA106K016RNJ") (field (name "Manufacturer") "Kyocera AVX"))
      (libsource (lib "easyedapro") (part "TAJA106K016RNJ"))
    )
    (comp (ref "CN3")
      (value "B3B-PH-K-S(LF)(SN)")
      (footprint "easyedapro:CONN-TH_B3B-PH-K-S")
      (fields (field (name "Manufacturer") "JST"))
      (libsource (lib "easyedapro") (part "B3B-PH-K-S(LF)(SN)"))
    )
    (comp (ref "H5")
      (value "PZ254V-11-02P")
      (footprint "easyedapro:HDR-TH_2P-P2.54-V-M")
      (fields (field (name "Manufacturer") "XFCN(兴飞)") (field (name "Add into BOM") "no"))
      (libsource (lib "easyedapro") (part "PZ254V-11-02P"))
    )
    (comp (ref "R34")
      (value "1kΩ")
      (fields
        (field (name "Manufacturer Part") "0402WGF1001TCE")
        (field (name "Manufacturer") "UNI-ROYAL(厚声)")
      )
      (libsource (lib "easyedapro") (part "Res"))
    )
    (comp (ref "R37")
      (value "22kΩ")
      (fields
        (field (name "Manufacturer Part") "0402WGF2202TCE")
        (field (name "Manufacturer") "UNI-ROYAL(厚声)")
      )
      (libsource (lib "easyedapro") (part "Res"))
    )
    (comp (ref "R39")
      (value "47kΩ")
      (footprint "easyedapro:R0402")
      (fields
        (field (name "Manufacturer Part") "0402WGF4702TCE")
        (field (name "Manufacturer") "UNI-ROYAL(厚声)")
      )
      (libsource (lib "easyedapro") (part "0402WGF4702TCE"))
    )
    (comp (ref "R40")
      (value "22kΩ")
      (fields
        (field (name "Manufacturer Part") "0402WGF2202TCE")
        (field (name "Manufacturer") "UNI-ROYAL(厚声)")
      )
      (libsource (lib "easyedapro") (part "Res"))
    )
    (comp (ref "R41")
      (value "47kΩ")
      (footprint "easyedapro:R0402")
      (fields
        (field (name "Manufacturer Part") "0402WGF4702TCE")
        (field (name "Manufacturer") "UNI-ROYAL(厚声)")
      )
      (libsource (lib "easyedapro") (part "0402WGF4702TCE"))
    )
    (comp (ref "R42")
      (value "10kΩ")
      (fields
        (field (name "Manufacturer Part") "0402WGF1002TCE")
        (field (name "Manufacturer") "UNI-ROYAL(厚声)")
      )
      (libsource (lib "easyedapro") (part "Res"))
    )
    (comp (ref "R43")
      (value "47kΩ")
      (footprint "easyedapro:R0402")
      (fields
        (field (name "Manufacturer Part") "0402WGF4702TCE")
        (field (name "Manufacturer") "UNI-ROYAL(厚声)")
      )
      (libsource (lib "easyedapro") (part "0402WGF4702TCE"))
    )
    (comp (ref "R44")
      (value "100kΩ")
      (footprint "easyedapro:RES-ADJ-TH_RK09K1130AJ3")
      (description "Resistance: Tolerance:±20% Tolerance:±20% Power(Watts):50mW Turns:- Rated Voltage:20V")
      (fields
        (field (name "Manufacturer Part") "RK09K1130AU2")
        (field (name "Manufacturer") "ALPSALPINE(阿尔卑斯阿尔派)")
      )
      (libsource (lib "easyedapro") (part "RK09K1130AU2"))
    )
    (comp (ref "R45")
      (value "22kΩ")
      (fields
        (field (name "Manufacturer Part") "0402WGF2202TCE")
        (field (name "Manufacturer") "UNI-ROYAL(厚声)")
      )
      (libsource (lib "easyedapro") (part "Res"))
    )
    (comp (ref "R46")
      (value "100kΩ")
      (footprint "easyedapro:RES-ADJ-TH_RK09K1130AJ3")
      (description "Resistance: Tolerance:±20% Tolerance:±20% Power(Watts):50mW Turns:- Rated Voltage:20V")
      (fields
        (field (name "Manufacturer Part") "RK09K1130AU2")
        (field (name "Manufacturer") "ALPSALPINE(阿尔卑斯阿尔派)")
      )
      (libsource (lib "easyedapro") (part "RK09K1130AU2"))
    )
    (comp (ref "R47")
      (value "10kΩ")
      (fields
        (field (name "Manufacturer Part") "0402WGF1002TCE")
        (field (name "Manufacturer") "UNI-ROYAL(厚声)")
      )
      (libsource (lib "easyedapro") (part "Res"))
    )
    (comp (ref "R48")
      (value "22kΩ")
      (fields
        (field (name "Manufacturer Part") "0402WGF2202TCE")
        (field (name "Manufacturer") "UNI-ROYAL(厚声)")
      )
      (libsource (lib "easyedapro") (part "Res"))
    )
    (comp (ref "R49")
      (value "1MΩ")
      (fields
        (field (name "Manufacturer Part") "0402WGF1004TCE")
        (field (name "Manufacturer") "UNI-ROYAL(厚声)")
      )
      (libsource (lib "easyedapro") (part "Res"))
    )
    (comp (ref "R50")
      (value "47kΩ")
      (footprint "easyedapro:R0402")
      (fields
        (field (name "Manufacturer Part") "0402WGF4702TCE")
        (field (name "Manufacturer") "UNI-ROYAL(厚声)")
      )
      (libsource (lib "easyedapro") (part "0402WGF4702TCE"))
    )
    (comp (ref "R51")
      (value "100kΩ")
      (footprint "easyedapro:RES-ADJ-TH_RK09K1130AJ3")
      (description "Resistance: Tolerance:±20% Tolerance:±20% Power(Watts):50mW Turns:- Rated Voltage:20V")
      (fields
        (field (name "Manufacturer Part") "RK09K1130AU2")
        (field (name "Manufacturer") "ALPSALPINE(阿尔卑斯阿尔派)")
      )
      (libsource (lib "easyedapro") (part "RK09K1130AU2"))
    )
    (comp (ref "R52")
      (value "15kΩ")
      (fields
        (field (name "Manufacturer Part") "0402WGF1502TCE")
        (field (name "Manufacturer") "UNI-ROYAL(厚声)")
      )
      (libsource (lib "easyedapro") (part "0402WGF1202TCE"))
    )
    (comp (ref "R82")
      (value "0Ω")
      (footprint "easyedapro:R0805")
      (fields
        (field (name "Manufacturer Part") "0805W8F0000T5E")
        (field (name "Manufacturer") "UNI-ROYAL(厚声)")
      )
      (libsource (lib "easyedapro") (part "0805W8F0000T5E"))
    )
    (comp (ref "R83")
      (value "0Ω")
      (footprint "easyedapro:R0805")
      (fields
        (field (name "Manufacturer Part") "0805W8F0000T5E")
        (field (name "Manufacturer") "UNI-ROYAL(厚声)")
      )
      (libsource (lib "easyedapro") (part "0805W8F0000T5E"))
    )
    (comp (ref "R84")
      (value "0Ω")
      (footprint "easyedapro:R0805")
      (fields
        (field (name "Manufacturer Part") "0805W8F0000T5E")
        (field (name "Manufacturer") "UNI-ROYAL(厚声)")
      )
      (libsource (lib "easyedapro") (part "0805W8F0000T5E"))
    )
    (comp (ref "U5")
      (value "MCP6002-I/SN")
      (footprint "easyedapro:SOIC-8_L4.9-W3.9-P1.27-LS6.0-BL")
      (fields (field (name "Manufacturer") "MICROCHIP(美国微芯)"))
      (libsource (lib "easyedapro") (part "MCP6002-I/SN"))
    )
    (comp (ref "U6")
      (value "LM1971MX/NOPB")
      (footprint "easyedapro:SOIC-8_L4.9-W3.9-P1.27-LS6.0-BL")
      (description "Supply Voltage:4.5V~12V Supply Voltage:4.5V~12V")
      (fields (field (name "Manufacturer") "TI(德州仪器)"))
      (libsource (lib "easyedapro") (part "LM1971MX/NOPB"))
    )
    (comp (ref "U7")
      (value "MCP6001T-I/OT")
      (footprint "easyedapro:SOT-23-5_L3.0-W1.7-P0.95-LS2.8-BR")
      (fields (field (name "Manufacturer") "MICROCHIP(美国微芯)"))
      (libsource (lib "easyedapro") (part "MCP6001T-I/OT"))
    )
    (comp (ref "C39")
      (value "100nF")
      (fields
        (field (name "Manufacturer Part") "CL05B104KO5NNNC")
        (field (name "Manufacturer") "SAMSUNG(三星)")
      )
      (libsource (lib "easyedapro") (part "CAP"))
    )
    (comp (ref "C40")
      (value "10uF")
      (footprint "easyedapro:C1206")
      (fields
        (field (name "Manufacturer Part") "CL31A106KBHNNNE")
        (field (name "Manufacturer") "SAMSUNG(三星)")
      )
      (libsource (lib "easyedapro") (part "CL31A106KBHNNNE"))
    )
    (comp (ref "C41")
      (value "10uF")
      (footprint "easyedapro:C1206")
      (fields
        (field (name "Manufacturer Part") "CL31A106KBHNNNE")
        (field (name "Manufacturer") "SAMSUNG(三星)")
      )
      (libsource (lib "easyedapro") (part "CL31A106KBHNNNE"))
    )
    (comp (ref "C42")
      (value "100nF")
      (fields
        (field (name "Manufacturer Part") "CL05B104KO5NNNC")
        (field (name "Manufacturer") "SAMSUNG(三星)")
      )
      (libsource (lib "easyedapro") (part "CAP"))
    )
    (comp (ref "C43")
      (value "10uF")
      (footprint "easyedapro:CAP-SMD_L3.2-W1.6-RD-C7171")
      (fields (field (name "Manufacturer Part") "TAJA106K016RNJ") (field (name "Manufacturer") "Kyocera AVX"))
      (libsource (lib "easyedapro") (part "TAJA106K016RNJ"))
    )
    (comp (ref "C44")
      (value "10uF")
      (footprint "easyedapro:CAP-SMD_L3.2-W1.6-RD-C7171")
      (fields (field (name "Manufacturer Part") "TAJA106K016RNJ") (field (name "Manufacturer") "Kyocera AVX"))
      (libsource (lib "easyedapro") (part "TAJA106K016RNJ"))
    )
    (comp (ref "C54")
      (value "20pF")
      (footprint "easyedapro:C0402")
      (fields (field (name "Manufacturer Part") "0402CG200J500NT") (field (name "Manufacturer") "FH(风华)"))
      (libsource (lib "easyedapro") (part "0402CG200J500NT"))
    )
    (comp (ref "C55")
      (value "20pF")
      (footprint "easyedapro:C0402")
      (fields (field (name "Manufacturer Part") "0402CG200J500NT") (field (name "Manufacturer") "FH(风华)"))
      (libsource (lib "easyedapro") (part "0402CG200J500NT"))
    )
    (comp (ref "C56")
      (value "20pF")
      (footprint "easyedapro:C0402")
      (fields (field (name "Manufacturer Part") "0402CG200J500NT") (field (name "Manufacturer") "FH(风华)"))
      (libsource (lib "easyedapro") (part "0402CG200J500NT"))
    )
    (comp (ref "C57")
      (value "20pF")
      (footprint "easyedapro:C0402")
      (fields (field (name "Manufacturer Part") "0402CG200J500NT") (field (name "Manufacturer") "FH(风华)"))
      (libsource (lib "easyedapro") (part "0402CG200J500NT"))
    )
    (comp (ref "CN5")
      (value "B3B-PH-K-S(LF)(SN)")
      (footprint "easyedapro:CONN-TH_B3B-PH-K-S")
      (fields (field (name "Manufacturer") "JST"))
      (libsource (lib "easyedapro") (part "B3B-PH-K-S(LF)(SN)"))
    )
    (comp (ref "CN6")
      (value "B3B-PH-K-S(LF)(SN)")
      (footprint "easyedapro:CONN-TH_B3B-PH-K-S")
      (fields (field (name "Manufacturer") "JST"))
      (libsource (lib "easyedapro") (part "B3B-PH-K-S(LF)(SN)"))
    )
    (comp (ref "R53")
      (value "11kΩ")
      (fields
        (field (name "Manufacturer Part") "0805W8F1102T5E")
        (field (name "Manufacturer") "UNI-ROYAL(厚声)")
      )
      (libsource (lib "easyedapro") (part "Res"))
    )
    (comp (ref "R54")
      (value "11kΩ")
      (fields
        (field (name "Manufacturer Part") "0805W8F1102T5E")
        (field (name "Manufacturer") "UNI-ROYAL(厚声)")
      )
      (libsource (lib "easyedapro") (part "Res"))
    )
    (comp (ref "R55")
      (value "47kΩ")
      (footprint "easyedapro:R0402")
      (fields
        (field (name "Manufacturer Part") "0402WGF4702TCE")
        (field (name "Manufacturer") "UNI-ROYAL(厚声)")
      )
      (libsource (lib "easyedapro") (part "0402WGF4702TCE"))
    )
    (comp (ref "R56")
      (value "47kΩ")
      (footprint "easyedapro:R0402")
      (fields
        (field (name "Manufacturer Part") "0402WGF4702TCE")
        (field (name "Manufacturer") "UNI-ROYAL(厚声)")
      )
      (libsource (lib "easyedapro") (part "0402WGF4702TCE"))
    )
    (comp (ref "R57")
      (value "22kΩ")
      (fields
        (field (name "Manufacturer Part") "0402WGF2202TCE")
        (field (name "Manufacturer") "UNI-ROYAL(厚声)")
      )
      (libsource (lib "easyedapro") (part "Res"))
    )
    (comp (ref "R58")
      (value "22kΩ")
      (fields
        (field (name "Manufacturer Part") "0402WGF2202TCE")
        (field (name "Manufacturer") "UNI-ROYAL(厚声)")
      )
      (libsource (lib "easyedapro") (part "Res"))
    )
    (comp (ref "R59")
      (value "22kΩ")
      (fields
        (field (name "Manufacturer Part") "0402WGF2202TCE")
        (field (name "Manufacturer") "UNI-ROYAL(厚声)")
      )
      (libsource (lib "easyedapro") (part "Res"))
    )
    (comp (ref "R60")
      (value "10kΩ")
      (fields
        (field (name "Manufacturer Part") "0402WGF1002TCE")
        (field (name "Manufacturer") "UNI-ROYAL(厚声)")
      )
      (libsource (lib "easyedapro") (part "Res"))
    )
    (comp (ref "R61")
      (value "10kΩ")
      (fields
        (field (name "Manufacturer Part") "0402WGF1002TCE")
        (field (name "Manufacturer") "UNI-ROYAL(厚声)")
      )
      (libsource (lib "easyedapro") (part "Res"))
    )
    (comp (ref "R62")
      (value "1kΩ")
      (fields
        (field (name "Manufacturer Part") "0402WGF1001TCE")
        (field (name "Manufacturer") "UNI-ROYAL(厚声)")
      )
      (libsource (lib "easyedapro") (part "Res"))
    )
    (comp (ref "R63")
      (value "1kΩ")
      (fields
        (field (name "Manufacturer Part") "0402WGF1001TCE")
        (field (name "Manufacturer") "UNI-ROYAL(厚声)")
      )
      (libsource (lib "easyedapro") (part "Res"))
    )
    (comp (ref "R64")
      (value "47kΩ")
      (fields
        (field (name "Manufacturer Part") "0805W8F4702T5E")
        (field (name "Manufacturer") "UNI-ROYAL(厚声)")
      )
      (libsource (lib "easyedapro") (part "Res"))
    )
    (comp (ref "R65")
      (value "10kΩ")
      (fields
        (field (name "Manufacturer Part") "0402WGF1002TCE")
        (field (name "Manufacturer") "UNI-ROYAL(厚声)")
      )
      (libsource (lib "easyedapro") (part "Res"))
    )
    (comp (ref "R66")
      (value "10kΩ")
      (fields
        (field (name "Manufacturer Part") "0402WGF1002TCE")
        (field (name "Manufacturer") "UNI-ROYAL(厚声)")
      )
      (libsource (lib "easyedapro") (part "Res"))
    )
    (comp (ref "R67")
      (value "10kΩ")
      (fields
        (field (name "Manufacturer Part") "0402WGF1002TCE")
        (field (name "Manufacturer") "UNI-ROYAL(厚声)")
      )
      (libsource (lib "easyedapro") (part "Res"))
    )
    (comp (ref "R68")
      (value "10kΩ")
      (fields
        (field (name "Manufacturer Part") "0402WGF1002TCE")
        (field (name "Manufacturer") "UNI-ROYAL(厚声)")
      )
      (libsource (lib "easyedapro") (part "Res"))
    )
    (comp (ref "R69")
      (value "1kΩ")
      (fields
        (field (name "Manufacturer Part") "0402WGF1001TCE")
        (field (name "Manufacturer") "UNI-ROYAL(厚声)")
      )
      (libsource (lib "easyedapro") (part "Res"))
    )
    (comp (ref "R70")
      (value "1kΩ")
      (fields
        (field (name "Manufacturer Part") "0402WGF1001TCE")
        (field (name "Manufacturer") "UNI-ROYAL(厚声)")
      )
      (libsource (lib "easyedapro") (part "Res"))
    )
    (comp (ref "R77")
      (value "47kΩ")
      (footprint "easyedapro:R0402")
      (fields
        (field (name "Manufacturer Part") "0402WGF4702TCE")
        (field (name "Manufacturer") "UNI-ROYAL(厚声)")
      )
      (libsource (lib "easyedapro") (part "0402WGF4702TCE"))
    )
    (comp (ref "R85")
      (value "0Ω")
      (footprint "easyedapro:R0805")
      (fields
        (field (name "Manufacturer Part") "0805W8F0000T5E")
        (field (name "Manufacturer") "UNI-ROYAL(厚声)")
      )
      (libsource (lib "easyedapro") (part "0805W8F0000T5E"))
    )
    (comp (ref "R86")
      (value "11kΩ")
      (fields
        (field (name "Manufacturer Part") "0805W8F1102T5E")
        (field (name "Manufacturer") "UNI-ROYAL(厚声)")
      )
      (libsource (lib "easyedapro") (part "Res"))
    )
    (comp (ref "R87")
      (value "22kΩ")
      (fields
        (field (name "Manufacturer Part") "0402WGF2202TCE")
        (field (name "Manufacturer") "UNI-ROYAL(厚声)")
      )
      (libsource (lib "easyedapro") (part "Res"))
    )
    (comp (ref "U9")
      (value "MCP6002-I/SN")
      (footprint "easyedapro:SOIC-8_L4.9-W3.9-P1.27-LS6.0-BL")
      (fields (field (name "Manufacturer") "MICROCHIP(美国微芯)"))
      (libsource (lib "easyedapro") (part "MCP6002-I/SN"))
    )
    (comp (ref "U10")
      (value "MCP6002-I/SN")
      (footprint "easyedapro:SOIC-8_L4.9-W3.9-P1.27-LS6.0-BL")
      (fields (field (name "Manufacturer") "MICROCHIP(美国微芯)"))
      (libsource (lib "easyedapro") (part "MCP6002-I/SN"))
    )
    (comp (ref "C51")
      (value "100nF")
      (fields
        (field (name "Manufacturer Part") "CL05B104KO5NNNC")
        (field (name "Manufacturer") "SAMSUNG(三星)")
      )
      (libsource (lib "easyedapro") (part "CAP"))
    )
    (comp (ref "C52")
      (value "100nF")
      (fields
        (field (name "Manufacturer Part") "CL05B104KO5NNNC")
        (field (name "Manufacturer") "SAMSUNG(三星)")
      )
      (libsource (lib "easyedapro") (part "CAP"))
    )
    (comp (ref "C53")
      (value "22uF")
      (footprint "easyedapro:CAP-SMD_L3.2-W1.6")
      (fields
        (field (name "Manufacturer Part") "CA45-A-16V-22uF-K")
        (field (name "Manufacturer") "CEC(振华新云)")
      )
      (libsource (lib "easyedapro") (part "CA45-A-16V-22UF-K"))
    )
    (comp (ref "C61")
      (value "1nF")
      (footprint "easyedapro:C0402")
      (description "Capacitance:1nF Tolerance:±10% Tolerance:±10% Voltage Rating:50V Temperature Coefficient:X7R")
      (fields (field (name "Manufacturer Part") "0402B102K500NT") (field (name "Manufacturer") "FH(风华)"))
      (libsource (lib "easyedapro") (part "0402B102K500NT"))
    )
    (comp (ref "C62")
      (value "100nF")
      (fields
        (field (name "Manufacturer Part") "CL05B104KO5NNNC")
        (field (name "Manufacturer") "SAMSUNG(三星)")
      )
      (libsource (lib "easyedapro") (part "CAP"))
    )
    (comp (ref "C63")
      (value "1nF")
      (footprint "easyedapro:C0402")
      (description "Capacitance:1nF Tolerance:±10% Tolerance:±10% Voltage Rating:50V Temperature Coefficient:X7R")
      (fields (field (name "Manufacturer Part") "0402B102K500NT") (field (name "Manufacturer") "FH(风华)"))
      (libsource (lib "easyedapro") (part "0402B102K500NT"))
    )
    (comp (ref "CN14")
      (value "HCZZ0039-4")
      (footprint "easyedapro:CONN-SMD_HCZZ0039-4")
      (fields (field (name "Manufacturer") "HC(虹成电子)"))
      (libsource (lib "easyedapro") (part "HCZZ0039-4"))
    )
    (comp (ref "CN15")
      (value "HC-1.0-5PWT")
      (footprint "easyedapro:CONN-SMD_5P-P1.00_HCTL_HC-1.0-5PWT")
      (fields (field (name "Manufacturer") "HCTL(华灿天禄)"))
      (libsource (lib "easyedapro") (part "HC-1.0-5PWT"))
    )
    (comp (ref "D9")
      (value "1N5819WS")
      (footprint "easyedapro:SOD-323_L1.8-W1.3-LS2.5-RD")
      (description "Reverse Voltage (Vr):40V Average Rectified Current (Io):1A Forward Voltage (Vf@If):600mV@1A")
      (fields (field (name "Manufacturer") "Hottech(合科泰)"))
      (libsource (lib "easyedapro") (part "1N5819WS"))
    )
    (comp (ref "H6")
      (value "PZ254V-11-02P")
      (footprint "easyedapro:HDR-TH_2P-P2.54-V-M")
      (fields (field (name "Manufacturer") "XFCN(兴飞)"))
      (libsource (lib "easyedapro") (part "PZ254V-11-02P"))
    )
    (comp (ref "R73")
      (value "5.1kΩ")
      (fields
        (field (name "Manufacturer Part") "0402WGF5101TCE")
        (field (name "Manufacturer") "UNI-ROYAL(厚声)")
      )
      (libsource (lib "easyedapro") (part "0402WGF1202TCE"))
    )
    (comp (ref "R74")
      (value "20kΩ")
      (footprint "easyedapro:R0402")
      (fields
        (field (name "Manufacturer Part") "0402WGF2002TCE")
        (field (name "Manufacturer") "UNI-ROYAL(厚声)")
      )
      (libsource (lib "easyedapro") (part "0402WGF2002TCE"))
    )
    (comp (ref "R75")
      (value "47kΩ")
      (footprint "easyedapro:R0402")
      (fields
        (field (name "Manufacturer Part") "0402WGF4702TCE")
        (field (name "Manufacturer") "UNI-ROYAL(厚声)")
      )
      (libsource (lib "easyedapro") (part "0402WGF4702TCE"))
    )
    (comp (ref "R76")
      (value "20kΩ")
      (footprint "easyedapro:R0402")
      (fields
        (field (name "Manufacturer Part") "0402WGF2002TCE")
        (field (name "Manufacturer") "UNI-ROYAL(厚声)")
      )
      (libsource (lib "easyedapro") (part "0402WGF2002TCE"))
    )
    (comp (ref "R91")
      (value "5.1kΩ")
      (fields
        (field (name "Manufacturer Part") "0402WGF5101TCE")
        (field (name "Manufacturer") "UNI-ROYAL(厚声)")
      )
      (libsource (lib "easyedapro") (part "0402WGF1202TCE"))
    )
    (comp (ref "R92")
      (value "5.1kΩ")
      (fields
        (field (name "Manufacturer Part") "0402WGF5101TCE")
        (field (name "Manufacturer") "UNI-ROYAL(厚声)")
      )
      (libsource (lib "easyedapro") (part "0402WGF1202TCE"))
    )
    (comp (ref "R99")
      (value "100Ω")
      (footprint "easyedapro:R0402")
      (fields
        (field (name "Manufacturer Part") "0402WGF1000TCE")
        (field (name "Manufacturer") "UNI-ROYAL(厚声)")
      )
      (libsource (lib "easyedapro") (part "0402WGF1000TCE"))
    )
    (comp (ref "R100")
      (value "10kΩ")
      (footprint "easyedapro:R0402")
      (fields
        (field (name "Manufacturer Part") "0402WGF1002TCE")
        (field (name "Manufacturer") "UNI-ROYAL(厚声)")
      )
      (libsource (lib "easyedapro") (part "0402WGF1002TCE"))
    )
    (comp (ref "R101")
      (value "0Ω")
      (footprint "easyedapro:R0603")
      (fields
        (field (name "Manufacturer Part") "0603WAF0000T5E")
        (field (name "Manufacturer") "UNI-ROYAL(厚声)")
      )
      (libsource (lib "easyedapro") (part "0603WAF0000T5E"))
    )
    (comp (ref "R102")
      (value "4.7kΩ")
      (footprint "easyedapro:R0402")
      (fields
        (field (name "Manufacturer Part") "0402WGF4701TCE")
        (field (name "Manufacturer") "UNI-ROYAL(厚声)")
      )
      (libsource (lib "easyedapro") (part "0402WGF4701TCE"))
    )
    (comp (ref "R103")
      (value "4.7kΩ")
      (footprint "easyedapro:R0402")
      (fields
        (field (name "Manufacturer Part") "0402WGF4701TCE")
        (field (name "Manufacturer") "UNI-ROYAL(厚声)")
      )
      (libsource (lib "easyedapro") (part "0402WGF4701TCE"))
    )
    (comp (ref "R104")
      (value "1kΩ")
      (fields
        (field (name "Manufacturer Part") "0402WGF1001TCE")
        (field (name "Manufacturer") "UNI-ROYAL(厚声)")
      )
      (libsource (lib "easyedapro") (part "Res"))
    )
    (comp (ref "SW1")
      (value "TS-1084-AR03526")
      (footprint "easyedapro:SW-SMD_TS-1084-AR03526")
      (fields (field (name "Manufacturer") "XUNPU(讯普)"))
      (libsource (lib "easyedapro") (part "TS-1084-AR03526"))
    )
    (comp (ref "SW2")
      (value "TS-1084-AR03526")
      (footprint "easyedapro:SW-SMD_TS-1084-AR03526")
      (fields (field (name "Manufacturer") "XUNPU(讯普)"))
      (libsource (lib "easyedapro") (part "TS-1084-AR03526"))
    )
    (comp (ref "U12")
      (value "STC8G1K08-38I-QFN20")
      (footprint "easyedapro:TQFN-20L_L3.0-W3.0-P0.40-BL-EP")
      (fields (field (name "Manufacturer") "STC"))
      (libsource (lib "easyedapro") (part "STC8G1K08-38I-QFN20"))
    )
    (comp (ref "U13")
      (value "310-47-104-41-001000")
      (footprint "easyedapro:HDR-TH_4P-P2.54-V-F_316-XX-104-41-007000")
      (fields (field (name "Manufacturer") "Mill-Max Mfg. Corp.") (field (name "Add into BOM") "no"))
      (libsource (lib "easyedapro") (part "310-47-104-41-001000"))
    )
  )
  (nets
    (net (code "1") (name "+5V") (class "Default")
      (node (ref "C18") (pin "2") (pinfunction "2_2") (pintype "input"))
      (node (ref "C20") (pin "2") (pinfunction "2_2") (pintype "input"))
      (node (ref "C30") (pin "1") (pinfunction "1_1") (pintype "input"))
      (node (ref "C31") (pin "1") (pinfunction "1_1") (pintype "input"))
      (node (ref "C32") (pin "1") (pinfunction "1_1") (pintype "input"))
      (node (ref "C36") (pin "2") (pinfunction "2_2") (pintype "input"))
      (node (ref "C39") (pin "2") (pinfunction "2_2") (pintype "input"))
      (node (ref "C42") (pin "1") (pinfunction "1_1") (pintype "input"))
      (node (ref "C47") (pin "1") (pinfunction "1_1") (pintype "input"))
      (node (ref "C48") (pin "2") (pinfunction "2_2") (pintype "input"))
      (node (ref "C52") (pin "2") (pinfunction "2_2") (pintype "input"))
      (node (ref "C53") (pin "1") (pinfunction "1_1") (pintype "input"))
      (node (ref "C6") (pin "2") (pinfunction "2_2") (pintype "input"))
      (node (ref "C8") (pin "2") (pinfunction "2_2") (pintype "input"))
      (node (ref "CN14") (pin "2") (pinfunction "2_2") (pintype "unspecified"))
      (node (ref "CN15") (pin "4") (pinfunction "4_4") (pintype "unspecified"))
      (node (ref "D1") (pin "1") (pinfunction "K_1") (pintype "input"))
      (node (ref "D2") (pin "1") (pinfunction "K_1") (pintype "input"))
      (node (ref "D5") (pin "1") (pinfunction "K_1") (pintype "input"))
      (node (ref "D6") (pin "1") (pinfunction "K_1") (pintype "input"))
      (node (ref "R100") (pin "2") (pinfunction "2_2") (pintype "input"))
      (node (ref "R102") (pin "2") (pinfunction "2_2") (pintype "input"))
      (node (ref "R103") (pin "2") (pinfunction "2_2") (pintype "input"))
      (node (ref "R71") (pin "1") (pinfunction "1_1") (pintype "input"))
      (node (ref "R74") (pin "2") (pinfunction "2_2") (pintype "input"))
      (node (ref "U1") (pin "5") (pinfunction "V+_5") (pintype "input"))
      (node (ref "U10") (pin "8") (pinfunction "VDD_8") (pintype "input"))
      (node (ref "U12") (pin "5") (pinfunction "Vcc/AVCC/ADC_VRef+_5") (pintype "unspecified"))
      (node (ref "U13") (pin "2") (pinfunction "2_2") (pintype "unspecified"))
      (node (ref "U2") (pin "8") (pinfunction "VDD_8") (pintype "input"))
      (node (ref "U3") (pin "5") (pinfunction "V+_5") (pintype "input"))
      (node (ref "U4") (pin "8") (pinfunction "VDD_8") (pintype "input"))
      (node (ref "U5") (pin "8") (pinfunction "VDD_8") (pintype "input"))
      (node (ref "U6") (pin "7") (pinfunction "VDD_7") (pintype "unspecified"))
      (node (ref "U7") (pin "5") (pinfunction "VDD_5") (pintype "input"))
      (node (ref "U8") (pin "3") (pinfunction "VOUT_3") (pintype "input"))
      (node (ref "U9") (pin "8") (pinfunction "VDD_8") (pintype "input"))
    )
    (net (code "2") (name "BATMON") (class "Default")
      (node (ref "C62") (pin "2") (pinfunction "2_2") (pintype "input"))
      (node (ref "C63") (pin "2") (pinfunction "2_2") (pintype "input"))
      (node (ref "R75") (pin "2") (pinfunction "2_2") (pintype "input"))
      (node (ref "R76") (pin "2") (pinfunction "2_2") (pintype "input"))
      (node (ref "U12") (pin "16") (pinfunction "CCP1/RXD2/ADC0/P1.0_16") (pintype "unspecified"))
    )
    (net (code "3") (name "GND") (class "Default")
      (node (ref "C18") (pin "1") (pinfunction "1_1") (pintype "input"))
      (node (ref "C20") (pin "1") (pinfunction "1_1") (pintype "input"))
      (node (ref "C25") (pin "1") (pinfunction "1_1") (pintype "input"))
      (node (ref "C30") (pin "2") (pinfunction "2_2") (pintype "input"))
      (node (ref "C31") (pin "2") (pinfunction "2_2") (pintype "input"))
      (node (ref "C32") (pin "2") (pinfunction "2_2") (pintype "input"))
      (node (ref "C36") (pin "1") (pinfunction "1_1") (pintype "input"))
      (node (ref "C39") (pin "1") (pinfunction "1_1") (pintype "input"))
      (node (ref "C42") (pin "2") (pinfunction "2_2") (pintype "input"))
      (node (ref "C45") (pin "2") (pinfunction "2_2") (pintype "input"))
      (node (ref "C46") (pin "1") (pinfunction "1_1") (pintype "input"))
      (node (ref "C47") (pin "2") (pinfunction "2_2") (pintype "input"))
      (node (ref "C48") (pin "1") (pinfunction "1_1") (pintype "input"))
      (node (ref "C49") (pin "2") (pinfunction "2_2") (pintype "input"))
      (node (ref "C50") (pin "1") (pinfunction "1_1") (pintype "input"))
      (node (ref "C51") (pin "1") (pinfunction "1_1") (pintype "input"))
      (node (ref "C52") (pin "1") (pinfunction "1_1") (pintype "input"))
      (node (ref "C53") (pin "2") (pinfunction "2_2") (pintype "input"))
      (node (ref "C58") (pin "2") (pinfunction "2_2") (pintype "input"))
      (node (ref "C6") (pin "1") (pinfunction "1_1") (pintype "input"))
      (node (ref "C61") (pin "1") (pinfunction "1_1") (pintype "input"))
      (node (ref "C62") (pin "1") (pinfunction "1_1") (pintype "input"))
      (node (ref "C63") (pin "1") (pinfunction "1_1") (pintype "input"))
      (node (ref "C8") (pin "1") (pinfunction "1_1") (pintype "input"))
      (node (ref "CN1") (pin "2") (pinfunction "2_2") (pintype "input"))
      (node (ref "CN13") (pin "2") (pinfunction "2_2") (pintype "unspecified"))
      (node (ref "CN14") (pin "1") (pinfunction "1_1") (pintype "unspecified"))
      (node (ref "CN14") (pin "5") (pinfunction "5_5") (pintype "unspecified"))
      (node (ref "CN14") (pin "6") (pinfunction "6_6") (pintype "unspecified"))
      (node (ref "CN15") (pin "5") (pinfunction "5_5") (pintype "unspecified"))
      (node (ref "CN15") (pin "6") (pinfunction "6_6") (pintype "unspecified"))
      (node (ref "CN15") (pin "7") (pinfunction "7_7") (pintype "unspecified"))
      (node (ref "CN2") (pin "2") (pinfunction "2_2") (pintype "input"))
      (node (ref "CN3") (pin "1") (pinfunction "1_1") (pintype "input"))
      (node (ref "CN5") (pin "3") (pinfunction "3_3") (pintype "input"))
      (node (ref "CN6") (pin "1") (pinfunction "1_1") (pintype "input"))
      (node (ref "D3") (pin "2") (pinfunction "A_2") (pintype "input"))
      (node (ref "D4") (pin "2") (pinfunction "A_2") (pintype "input"))
      (node (ref "D7") (pin "2") (pinfunction "A_2") (pintype "input"))
      (node (ref "D8") (pin "2") (pinfunction "A_2") (pintype "input"))
      (node (ref "H6") (pin "1") (pinfunction "1_1") (pintype "input"))
      (node (ref "R13") (pin "4") (pinfunction "4_4") (pintype "input"))
      (node (ref "R13") (pin "5") (pinfunction "5_5") (pintype "input"))
      (node (ref "R23") (pin "4") (pinfunction "4_4") (pintype "input"))
      (node (ref "R23") (pin "5") (pinfunction "5_5") (pintype "input"))
      (node (ref "R29") (pin "4") (pinfunction "4_4") (pintype "input"))
      (node (ref "R29") (pin "5") (pinfunction "5_5") (pintype "input"))
      (node (ref "R44") (pin "4") (pinfunction "4_4") (pintype "input"))
      (node (ref "R44") (pin "5") (pinfunction "5_5") (pintype "input"))
      (node (ref "R46") (pin "4") (pinfunction "4_4") (pintype "input"))
      (node (ref "R46") (pin "5") (pinfunction "5_5") (pintype "input"))
      (node (ref "R51") (pin "4") (pinfunction "4_4") (pintype "input"))
      (node (ref "R51") (pin "5") (pinfunction "5_5") (pintype "input"))
      (node (ref "R60") (pin "2") (pinfunction "2_2") (pintype "input"))
      (node (ref "R61") (pin "1") (pinfunction "1_1") (pintype "input"))
      (node (ref "R67") (pin "1") (pinfunction "1_1") (pintype "input"))
      (node (ref "R68") (pin "2") (pinfunction "2_2") (pintype "input"))
      (node (ref "R7") (pin "4") (pinfunction "4_4") (pintype "input"))
      (node (ref "R7") (pin "5") (pinfunction "5_5") (pintype "input"))
      (node (ref "R72") (pin "2") (pinfunction "2_2") (pintype "input"))
      (node (ref "R76") (pin "1") (pinfunction "1_1") (pintype "input"))
      (node (ref "R93") (pin "1") (pinfunction "1_1") (pintype "input"))
      (node (ref "R94") (pin "1") (pinfunction "1_1") (pintype "input"))
      (node (ref "R95") (pin "1") (pinfunction "1_1") (pintype "input"))
      (node (ref "R96") (pin "1") (pinfunction "1_1") (pintype "input"))
      (node (ref "SW1") (pin "2") (pinfunction "2_2") (pintype "unspecified"))
      (node (ref "SW1") (pin "3") (pinfunction "3_3") (pintype "unspecified"))
      (node (ref "SW1") (pin "4") (pinfunction "4_4") (pintype "unspecified"))
      (node (ref "SW2") (pin "2") (pinfunction "2_2") (pintype "unspecified"))
      (node (ref "SW2") (pin "3") (pinfunction "3_3") (pintype "unspecified"))
      (node (ref "SW2") (pin "4") (pinfunction "4_4") (pintype "unspecified"))
      (node (ref "U1") (pin "2") (pinfunction "V-_2") (pintype "input"))
      (node (ref "U10") (pin "4") (pinfunction "VSS_4") (pintype "input"))
      (node (ref "U12") (pin "7") (pinfunction "Gnd/AGnd_7") (pintype "unspecified"))
      (node (ref "U2") (pin "4") (pinfunction "VSS_4") (pintype "input"))
      (node (ref "U3") (pin "2") (pinfunction "V-_2") (pintype "input"))
      (node (ref "U4") (pin "4") (pinfunction "VSS_4") (pintype "input"))
      (node (ref "U5") (pin "4") (pinfunction "VSS_4") (pintype "input"))
      (node (ref "U6") (pin "3") (pinfunction "GND_3") (pintype "unspecified"))
      (node (ref "U7") (pin "2") (pinfunction "VSS_2") (pintype "input"))
      (node (ref "U8") (pin "1") (pinfunction "GND_1") (pintype "input"))
      (node (ref "U9") (pin "4") (pinfunction "VSS_4") (pintype "input"))
    )
    (net (code "4") (name "MICOUT1") (class "Default")
      (node (ref "C12") (pin "2") (pinfunction "2_2") (pintype "input"))
      (node (ref "R53") (pin "1") (pinfunction "1_1") (pintype "input"))
    )
    (net (code "5") (name "MICOUT2") (class "Default")
      (node (ref "C24") (pin "2") (pinfunction "2_2") (pintype "input"))
      (node (ref "R54") (pin "1") (pinfunction "1_1") (pintype "input"))
    )
    (net (code "6") (name "MUSICOUT") (class "Default")
      (node (ref "CN5") (pin "2") (pinfunction "2_2") (pintype "input"))
      (node (ref "R62") (pin "2") (pinfunction "2_2") (pintype "input"))
    )
    (net (code "7") (name "MUSICOUT1") (class "Default")
      (node (ref "C38") (pin "2") (pinfunction "2_2") (pintype "input"))
      (node (ref "R56") (pin "1") (pinfunction "1_1") (pintype "input"))
      (node (ref "U9") (pin "5") (pinfunction "VINB+_5") (pintype "input"))
    )
    (net (code "8") (name "Net-(C1-Pad1)") (class "Default")
      (node (ref "C1") (pin "1") (pinfunction "1_1") (pintype "input"))
      (node (ref "CN1") (pin "3") (pinfunction "3_3") (pintype "input"))
      (node (ref "R95") (pin "2") (pinfunction "2_2") (pintype "input"))
    )
    (net (code "9") (name "Net-(C1-Pad2)") (class "Default")
      (node (ref "C1") (pin "2") (pinfunction "2_2") (pintype "input"))
      (node (ref "R1") (pin "1") (pinfunction "1_1") (pintype "input"))
    )
    (net (code "10") (name "Net-(C2-Pad1)") (class "Default")
      (node (ref "C2") (pin "1") (pinfunction "1_1") (pintype "input"))
      (node (ref "CN1") (pin "1") (pinfunction "1_1") (pintype "input"))
      (node (ref "R96") (pin "2") (pinfunction "2_2") (pintype "input"))
    )
    (net (code "11") (name "Net-(C2-Pad2)") (class "Default")
      (node (ref "C2") (pin "2") (pinfunction "2_2") (pintype "input"))
      (node (ref "R2") (pin "1") (pinfunction "1_1") (pintype "input"))
    )
    (net (code "12") (name "Net-(C3-Pad1)") (class "Default")
      (node (ref "C3") (pin "1") (pinfunction "1_1") (pintype "input"))
      (node (ref "R1") (pin "2") (pinfunction "2_2") (pintype "input"))
      (node (ref "R3") (pin "1") (pinfunction "1_1") (pintype "input"))
    )
    (net (code "13") (name "Net-(C3-Pad2)") (class "Default")
      (node (ref "C3") (pin "2") (pinfunction "2_2") (pintype "input"))
      (node (ref "R2") (pin "2") (pinfunction "2_2") (pintype "input"))
      (node (ref "R4") (pin "1") (pinfunction "1_1") (pintype "input"))
    )
    (net (code "14") (name "Net-(C9-Pad1)") (class "Default")
      (node (ref "C9") (pin "1") (pinfunction "1_1") (pintype "input"))
      (node (ref "R11") (pin "2") (pinfunction "2_2") (pintype "input"))
      (node (ref "R97") (pin "2") (pinfunction "2_2") (pintype "input"))
    )
    (net (code "15") (name "Net-(C9-Pad2)") (class "Default")
      (node (ref "C9") (pin "2") (pinfunction "2_2") (pintype "input"))
      (node (ref "R14") (pin "1") (pinfunction "1_1") (pintype "input"))
    )
    (net (code "16") (name "Net-(C10-Pad1)") (class "Default")
      (node (ref "C10") (pin "1") (pinfunction "1_1") (pintype "input"))
      (node (ref "R11") (pin "1") (pinfunction "1_1") (pintype "input"))
      (node (ref "R78") (pin "2") (pinfunction "2_2") (pintype "input"))
    )
    (net (code "17") (name "Net-(C10-Pad2)") (class "Default")
      (node (ref "C10") (pin "2") (pinfunction "2_2") (pintype "input"))
      (node (ref "R15") (pin "1") (pinfunction "1_1") (pintype "input"))
    )
    (net (code "18") (name "Net-(C12-Pad1)") (class "Default")
      (node (ref "C12") (pin "1") (pinfunction "1_1") (pintype "input"))
      (node (ref "R79") (pin "2") (pinfunction "2_2") (pintype "input"))
    )
    (net (code "19") (name "Net-(C13-Pad1)") (class "Default")
      (node (ref "C13") (pin "1") (pinfunction "1_1") (pintype "input"))
      (node (ref "CN2") (pin "3") (pinfunction "3_3") (pintype "input"))
      (node (ref "R93") (pin "2") (pinfunction "2_2") (pintype "input"))
    )
    (net (code "20") (name "Net-(C13-Pad2)") (class "Default")
      (node (ref "C13") (pin "2") (pinfunction "2_2") (pintype "input"))
      (node (ref "R17") (pin "1") (pinfunction "1_1") (pintype "input"))
    )
    (net (code "21") (name "Net-(C14-Pad1)") (class "Default")
      (node (ref "C14") (pin "1") (pinfunction "1_1") (pintype "input"))
      (node (ref "CN2") (pin "1") (pinfunction "1_1") (pintype "input"))
      (node (ref "R94") (pin "2") (pinfunction "2_2") (pintype "input"))
    )
    (net (code "22") (name "Net-(C14-Pad2)") (class "Default")
      (node (ref "C14") (pin "2") (pinfunction "2_2") (pintype "input"))
      (node (ref "R18") (pin "1") (pinfunction "1_1") (pintype "input"))
    )
    (net (code "23") (name "Net-(C15-Pad1)") (class "Default")
      (node (ref "C15") (pin "1") (pinfunction "1_1") (pintype "input"))
      (node (ref "R17") (pin "2") (pinfunction "2_2") (pintype "input"))
      (node (ref "R19") (pin "1") (pinfunction "1_1") (pintype "input"))
    )
    (net (code "24") (name "Net-(C15-Pad2)") (class "Default")
      (node (ref "C15") (pin "2") (pinfunction "2_2") (pintype "input"))
      (node (ref "R18") (pin "2") (pinfunction "2_2") (pintype "input"))
      (node (ref "R20") (pin "1") (pinfunction "1_1") (pintype "input"))
    )
    (net (code "25") (name "Net-(C21-Pad1)") (class "Default")
      (node (ref "C21") (pin "1") (pinfunction "1_1") (pintype "input"))
      (node (ref "R27") (pin "2") (pinfunction "2_2") (pintype "input"))
      (node (ref "R98") (pin "2") (pinfunction "2_2") (pintype "input"))
    )
    (net (code "26") (name "Net-(C21-Pad2)") (class "Default")
      (node (ref "C21") (pin "2") (pinfunction "2_2") (pintype "input"))
      (node (ref "R30") (pin "1") (pinfunction "1_1") (pintype "input"))
    )
    (net (code "27") (name "Net-(C22-Pad1)") (class "Default")
      (node (ref "C22") (pin "1") (pinfunction "1_1") (pintype "input"))
      (node (ref "R27") (pin "1") (pinfunction "1_1") (pintype "input"))
      (node (ref "R81") (pin "2") (pinfunction "2_2") (pintype "input"))
    )
    (net (code "28") (name "Net-(C22-Pad2)") (class "Default")
      (node (ref "C22") (pin "2") (pinfunction "2_2") (pintype "input"))
      (node (ref "R31") (pin "1") (pinfunction "1_1") (pintype "input"))
    )
    (net (code "29") (name "Net-(C24-Pad1)") (class "Default")
      (node (ref "C24") (pin "1") (pinfunction "1_1") (pintype "input"))
      (node (ref "R80") (pin "2") (pinfunction "2_2") (pintype "input"))
    )
    (net (code "30") (name "Net-(C25-Pad2)") (class "Default")
      (node (ref "C25") (pin "2") (pinfunction "2_2") (pintype "input"))
      (node (ref "C27") (pin "1") (pinfunction "1_1") (pintype "input"))
      (node (ref "R34") (pin "1") (pinfunction "1_1") (pintype "input"))
    )
    (net (code "31") (name "Net-(C27-Pad2)") (class "Default")
      (node (ref "C27") (pin "2") (pinfunction "2_2") (pintype "input"))
      (node (ref "R37") (pin "1") (pinfunction "1_1") (pintype "input"))
    )
    (net (code "32") (name "Net-(C29-Pad1)") (class "Default")
      (node (ref "C29") (pin "1") (pinfunction "1_1") (pintype "input"))
      (node (ref "R83") (pin "2") (pinfunction "2_2") (pintype "input"))
    )
    (net (code "33") (name "Net-(C33-Pad1)") (class "Default")
      (node (ref "C33") (pin "1") (pinfunction "1_1") (pintype "input"))
      (node (ref "C35") (pin "1") (pinfunction "1_1") (pintype "input"))
      (node (ref "R44") (pin "2") (pinfunction "2_2") (pintype "input"))
      (node (ref "R45") (pin "2") (pinfunction "2_2") (pintype "input"))
    )
    (net (code "34") (name "Net-(C33-Pad2)") (class "Default")
      (node (ref "C33") (pin "2") (pinfunction "2_2") (pintype "input"))
      (node (ref "R40") (pin "2") (pinfunction "2_2") (pintype "input"))
      (node (ref "R44") (pin "3") (pinfunction "3_3") (pintype "input"))
    )
    (net (code "35") (name "Net-(C34-Pad1)") (class "Default")
      (node (ref "C34") (pin "1") (pinfunction "1_1") (pintype "input"))
      (node (ref "R46") (pin "2") (pinfunction "2_2") (pintype "input"))
    )
    (net (code "36") (name "Net-(C35-Pad2)") (class "Default")
      (node (ref "C35") (pin "2") (pinfunction "2_2") (pintype "input"))
      (node (ref "R44") (pin "1") (pinfunction "1_1") (pintype "input"))
      (node (ref "R48") (pin "1") (pinfunction "1_1") (pintype "input"))
    )
    (net (code "37") (name "Net-(C38-Pad1)") (class "Default")
      (node (ref "C38") (pin "1") (pinfunction "1_1") (pintype "input"))
      (node (ref "R84") (pin "2") (pinfunction "2_2") (pintype "input"))
    )
    (net (code "38") (name "Net-(C40-Pad2)") (class "Default")
      (node (ref "C40") (pin "2") (pinfunction "2_2") (pintype "input"))
      (node (ref "R60") (pin "1") (pinfunction "1_1") (pintype "input"))
      (node (ref "R63") (pin "1") (pinfunction "1_1") (pintype "input"))
    )
    (net (code "39") (name "Net-(C41-Pad2)") (class "Default")
      (node (ref "C41") (pin "2") (pinfunction "2_2") (pintype "input"))
      (node (ref "R61") (pin "2") (pinfunction "2_2") (pintype "input"))
      (node (ref "R62") (pin "1") (pinfunction "1_1") (pintype "input"))
    )
    (net (code "40") (name "Net-(C43-Pad2)") (class "Default")
      (node (ref "C43") (pin "2") (pinfunction "2_2") (pintype "input"))
      (node (ref "R67") (pin "2") (pinfunction "2_2") (pintype "input"))
      (node (ref "R69") (pin "1") (pinfunction "1_1") (pintype "input"))
    )
    (net (code "41") (name "Net-(C44-Pad2)") (class "Default")
      (node (ref "C44") (pin "2") (pinfunction "2_2") (pintype "input"))
      (node (ref "R68") (pin "1") (pinfunction "1_1") (pintype "input"))
      (node (ref "R70") (pin "1") (pinfunction "1_1") (pintype "input"))
    )
    (net (code "42") (name "Net-(CN3-Pad2)") (class "Default")
      (node (ref "CN3") (pin "2") (pinfunction "2_2") (pintype "input"))
      (node (ref "R34") (pin "2") (pinfunction "2_2") (pintype "input"))
    )
    (net (code "43") (name "Net-(CN6-Pad2)") (class "Default")
      (node (ref "CN6") (pin "2") (pinfunction "2_2") (pintype "input"))
      (node (ref "R70") (pin "2") (pinfunction "2_2") (pintype "input"))
    )
    (net (code "44") (name "Net-(CN6-Pad3)") (class "Default")
      (node (ref "CN6") (pin "3") (pinfunction "3_3") (pintype "input"))
      (node (ref "R69") (pin "2") (pinfunction "2_2") (pintype "input"))
    )
    (net (code "45") (name "Net-(CN15-Pad1)") (class "Default")
      (node (ref "CN15") (pin "1") (pinfunction "1_1") (pintype "unspecified"))
      (node (ref "R101") (pin "2") (pinfunction "2_2") (pintype "input"))
    )
    (net (code "46") (name "Net-(CN15-Pad3)") (class "Default")
      (node (ref "CN15") (pin "3") (pinfunction "3_3") (pintype "unspecified"))
      (node (ref "R99") (pin "2") (pinfunction "2_2") (pintype "input"))
    )
    (net (code "47") (name "Net-(D1-A)") (class "Default")
      (node (ref "C5") (pin "1") (pinfunction "1_1") (pintype "input"))
      (node (ref "D1") (pin "2") (pinfunction "A_2") (pintype "input"))
      (node (ref "D3") (pin "1") (pinfunction "K_1") (pintype "input"))
      (node (ref "R3") (pin "2") (pinfunction "2_2") (pintype "input"))
      (node (ref "R6") (pin "1") (pinfunction "1_1") (pintype "input"))
      (node (ref "U1") (pin "3") (pinfunction "IN-_3") (pintype "input"))
    )
    (net (code "48") (name "Net-(D2-A)") (class "Default")
      (node (ref "C4") (pin "1") (pinfunction "1_1") (pintype "input"))
      (node (ref "D2") (pin "2") (pinfunction "A_2") (pintype "input"))
      (node (ref "D4") (pin "1") (pinfunction "K_1") (pintype "input"))
      (node (ref "R4") (pin "2") (pinfunction "2_2") (pintype "input"))
      (node (ref "R5") (pin "1") (pinfunction "1_1") (pintype "input"))
      (node (ref "U1") (pin "1") (pinfunction "IN+_1") (pintype "input"))
    )
    (net (code "49") (name "Net-(D5-A)") (class "Default")
      (node (ref "C17") (pin "1") (pinfunction "1_1") (pintype "input"))
      (node (ref "D5") (pin "2") (pinfunction "A_2") (pintype "input"))
      (node (ref "D7") (pin "1") (pinfunction "K_1") (pintype "input"))
      (node (ref "R19") (pin "2") (pinfunction "2_2") (pintype "input"))
      (node (ref "R22") (pin "1") (pinfunction "1_1") (pintype "input"))
      (node (ref "U3") (pin "3") (pinfunction "IN-_3") (pintype "input"))
    )
    (net (code "50") (name "Net-(D6-A)") (class "Default")
      (node (ref "C16") (pin "1") (pinfunction "1_1") (pintype "input"))
      (node (ref "D6") (pin "2") (pinfunction "A_2") (pintype "input"))
      (node (ref "D8") (pin "1") (pinfunction "K_1") (pintype "input"))
      (node (ref "R20") (pin "2") (pinfunction "2_2") (pintype "input"))
      (node (ref "R21") (pin "1") (pinfunction "1_1") (pintype "input"))
      (node (ref "U3") (pin "1") (pinfunction "IN+_1") (pintype "input"))
    )
    (net (code "51") (name "Net-(D9-K)") (class "Default")
      (node (ref "CN15") (pin "2") (pinfunction "2_2") (pintype "unspecified"))
      (node (ref "D9") (pin "1") (pinfunction "K_1") (pintype "input"))
    )
    (net (code "52") (name "Net-(R7-Pad2)") (class "Default")
      (node (ref "R7") (pin "2") (pinfunction "2_2") (pintype "input"))
      (node (ref "R79") (pin "1") (pinfunction "1_1") (pintype "input"))
      (node (ref "R9") (pin "2") (pinfunction "2_2") (pintype "input"))
    )
    (net (code "53") (name "Net-(R13-Pad1)") (class "Default")
      (node (ref "R13") (pin "1") (pinfunction "1_1") (pintype "input"))
      (node (ref "R97") (pin "1") (pinfunction "1_1") (pintype "input"))
    )
    (net (code "54") (name "Net-(R13-Pad3)") (class "Default")
      (node (ref "R13") (pin "3") (pinfunction "3_3") (pintype "input"))
      (node (ref "R15") (pin "2") (pinfunction "2_2") (pintype "input"))
      (node (ref "R16") (pin "1") (pinfunction "1_1") (pintype "input"))
    )
    (net (code "55") (name "Net-(R23-Pad2)") (class "Default")
      (node (ref "R23") (pin "2") (pinfunction "2_2") (pintype "input"))
      (node (ref "R25") (pin "2") (pinfunction "2_2") (pintype "input"))
      (node (ref "R80") (pin "1") (pinfunction "1_1") (pintype "input"))
    )
    (net (code "56") (name "Net-(R29-Pad1)") (class "Default")
      (node (ref "R29") (pin "1") (pinfunction "1_1") (pintype "input"))
      (node (ref "R98") (pin "1") (pinfunction "1_1") (pintype "input"))
    )
    (net (code "57") (name "Net-(R29-Pad3)") (class "Default")
      (node (ref "R29") (pin "3") (pinfunction "3_3") (pintype "input"))
      (node (ref "R31") (pin "2") (pinfunction "2_2") (pintype "input"))
      (node (ref "R32") (pin "1") (pinfunction "1_1") (pintype "input"))
    )
    (net (code "58") (name "Net-(R40-Pad1)") (class "Default")
      (node (ref "R40") (pin "1") (pinfunction "1_1") (pintype "input"))
      (node (ref "R42") (pin "1") (pinfunction "1_1") (pintype "input"))
      (node (ref "R82") (pin "2") (pinfunction "2_2") (pintype "input"))
    )
    (net (code "59") (name "Net-(R42-Pad2)") (class "Default")
      (node (ref "R42") (pin "2") (pinfunction "2_2") (pintype "input"))
      (node (ref "R46") (pin "3") (pinfunction "3_3") (pintype "input"))
    )
    (net (code "60") (name "Net-(R46-Pad1)") (class "Default")
      (node (ref "R46") (pin "1") (pinfunction "1_1") (pintype "input"))
      (node (ref "R47") (pin "1") (pinfunction "1_1") (pintype "input"))
    )
    (net (code "61") (name "Net-(R51-Pad2)") (class "Default")
      (node (ref "R51") (pin "2") (pinfunction "2_2") (pintype "input"))
      (node (ref "R52") (pin "2") (pinfunction "2_2") (pintype "input"))
      (node (ref "R84") (pin "1") (pinfunction "1_1") (pintype "input"))
    )
    (net (code "62") (name "Net-(R58-Pad2)") (class "Default")
      (node (ref "R58") (pin "2") (pinfunction "2_2") (pintype "input"))
      (node (ref "R59") (pin "2") (pinfunction "2_2") (pintype "input"))
      (node (ref "R85") (pin "2") (pinfunction "2_2") (pintype "input"))
    )
    (net (code "63") (name "Net-(R73-Pad1)") (class "Default")
      (node (ref "R73") (pin "1") (pinfunction "1_1") (pintype "input"))
      (node (ref "U13") (pin "4") (pinfunction "4_4") (pintype "unspecified"))
    )
    (net (code "64") (name "Net-(R91-Pad1)") (class "Default")
      (node (ref "R91") (pin "1") (pinfunction "1_1") (pintype "input"))
      (node (ref "U13") (pin "3") (pinfunction "3_3") (pintype "unspecified"))
    )
    (net (code "65") (name "Net-(R92-Pad1)") (class "Default")
      (node (ref "R92") (pin "1") (pinfunction "1_1") (pintype "input"))
      (node (ref "U13") (pin "1") (pinfunction "1_1") (pintype "unspecified"))
    )
    (net (code "66") (name "Net-(U1-OUT)") (class "Default")
      (node (ref "C5") (pin "2") (pinfunction "2_2") (pintype "input"))
      (node (ref "R6") (pin "2") (pinfunction "2_2") (pintype "input"))
      (node (ref "U1") (pin "4") (pinfunction "OUT_4") (pintype "input"))
      (node (ref "U2") (pin "3") (pinfunction "VINA+_3") (pintype "input"))
    )
    (net (code "67") (name "Net-(U2A-VINB+)") (class "Default")
      (node (ref "R12") (pin "1") (pinfunction "1_1") (pintype "input"))
      (node (ref "U2") (pin "5") (pinfunction "VINB+_5") (pintype "input"))
    )
    (net (code "68") (name "Net-(U2A-VINB-)") (class "Default")
      (node (ref "C11") (pin "1") (pinfunction "1_1") (pintype "input"))
      (node (ref "R13") (pin "2") (pinfunction "2_2") (pintype "input"))
      (node (ref "U2") (pin "6") (pinfunction "VINB-_6") (pintype "input"))
    )
    (net (code "69") (name "Net-(U2A-VOUTB)") (class "Default")
      (node (ref "C11") (pin "2") (pinfunction "2_2") (pintype "input"))
      (node (ref "R14") (pin "2") (pinfunction "2_2") (pintype "input"))
      (node (ref "R16") (pin "2") (pinfunction "2_2") (pintype "input"))
      (node (ref "R7") (pin "3") (pinfunction "3_3") (pintype "input"))
      (node (ref "U2") (pin "7") (pinfunction "VOUTB_7") (pintype "output"))
    )
    (net (code "70") (name "Net-(U2B-VINA-)") (class "Default")
      (node (ref "C7") (pin "1") (pinfunction "1_1") (pintype "input"))
      (node (ref "R10") (pin "1") (pinfunction "1_1") (pintype "input"))
      (node (ref "R8") (pin "1") (pinfunction "1_1") (pintype "input"))
      (node (ref "U2") (pin "2") (pinfunction "VINA-_2") (pintype "input"))
    )
    (net (code "71") (name "Net-(U2B-VOUTA)") (class "Default")
      (node (ref "C7") (pin "2") (pinfunction "2_2") (pintype "input"))
      (node (ref "R10") (pin "2") (pinfunction "2_2") (pintype "input"))
      (node (ref "R78") (pin "1") (pinfunction "1_1") (pintype "input"))
      (node (ref "U2") (pin "1") (pinfunction "VOUTA_1") (pintype "output"))
    )
    (net (code "72") (name "Net-(U3-OUT)") (class "Default")
      (node (ref "C17") (pin "2") (pinfunction "2_2") (pintype "input"))
      (node (ref "R22") (pin "2") (pinfunction "2_2") (pintype "input"))
      (node (ref "U3") (pin "4") (pinfunction "OUT_4") (pintype "input"))
      (node (ref "U4") (pin "3") (pinfunction "VINA+_3") (pintype "input"))
    )
    (net (code "73") (name "Net-(U4A-VINB+)") (class "Default")
      (node (ref "R28") (pin "1") (pinfunction "1_1") (pintype "input"))
      (node (ref "U4") (pin "5") (pinfunction "VINB+_5") (pintype "input"))
    )
    (net (code "74") (name "Net-(U4A-VINB-)") (class "Default")
      (node (ref "C23") (pin "1") (pinfunction "1_1") (pintype "input"))
      (node (ref "R29") (pin "2") (pinfunction "2_2") (pintype "input"))
      (node (ref "U4") (pin "6") (pinfunction "VINB-_6") (pintype "input"))
    )
    (net (code "75") (name "Net-(U4A-VOUTB)") (class "Default")
      (node (ref "C23") (pin "2") (pinfunction "2_2") (pintype "input"))
      (node (ref "R23") (pin "3") (pinfunction "3_3") (pintype "input"))
      (node (ref "R30") (pin "2") (pinfunction "2_2") (pintype "input"))
      (node (ref "R32") (pin "2") (pinfunction "2_2") (pintype "input"))
      (node (ref "U4") (pin "7") (pinfunction "VOUTB_7") (pintype "output"))
    )
    (net (code "76") (name "Net-(U4B-VINA-)") (class "Default")
      (node (ref "C19") (pin "1") (pinfunction "1_1") (pintype "input"))
      (node (ref "R24") (pin "1") (pinfunction "1_1") (pintype "input"))
      (node (ref "R26") (pin "1") (pinfunction "1_1") (pintype "input"))
      (node (ref "U4") (pin "2") (pinfunction "VINA-_2") (pintype "input"))
    )
    (net (code "77") (name "Net-(U4B-VOUTA)") (class "Default")
      (node (ref "C19") (pin "2") (pinfunction "2_2") (pintype "input"))
      (node (ref "R26") (pin "2") (pinfunction "2_2") (pintype "input"))
      (node (ref "R81") (pin "1") (pinfunction "1_1") (pintype "input"))
      (node (ref "U4") (pin "1") (pinfunction "VOUTA_1") (pintype "output"))
    )
    (net (code "78") (name "Net-(U5A-VINB+)") (class "Default")
      (node (ref "R50") (pin "1") (pinfunction "1_1") (pintype "input"))
      (node (ref "U5") (pin "5") (pinfunction "VINB+_5") (pintype "input"))
    )
    (net (code "79") (name "Net-(U5A-VINB-)") (class "Default")
      (node (ref "C34") (pin "2") (pinfunction "2_2") (pintype "input"))
      (node (ref "C37") (pin "1") (pinfunction "1_1") (pintype "input"))
      (node (ref "R45") (pin "1") (pinfunction "1_1") (pintype "input"))
      (node (ref "R49") (pin "1") (pinfunction "1_1") (pintype "input"))
      (node (ref "U5") (pin "6") (pinfunction "VINB-_6") (pintype "input"))
    )
    (net (code "80") (name "Net-(U5A-VOUTB)") (class "Default")
      (node (ref "C37") (pin "2") (pinfunction "2_2") (pintype "input"))
      (node (ref "R47") (pin "2") (pinfunction "2_2") (pintype "input"))
      (node (ref "R48") (pin "2") (pinfunction "2_2") (pintype "input"))
      (node (ref "R49") (pin "2") (pinfunction "2_2") (pintype "input"))
      (node (ref "R83") (pin "1") (pinfunction "1_1") (pintype "input"))
      (node (ref "U5") (pin "7") (pinfunction "VOUTB_7") (pintype "output"))
    )
    (net (code "81") (name "Net-(U5B-VINA+)") (class "Default")
      (node (ref "R37") (pin "2") (pinfunction "2_2") (pintype "input"))
      (node (ref "R39") (pin "1") (pinfunction "1_1") (pintype "input"))
      (node (ref "U5") (pin "3") (pinfunction "VINA+_3") (pintype "input"))
    )
    (net (code "82") (name "Net-(U5B-VINA-)") (class "Default")
      (node (ref "R82") (pin "1") (pinfunction "1_1") (pintype "input"))
      (node (ref "U5") (pin "1") (pinfunction "VOUTA_1") (pintype "output"))
      (node (ref "U5") (pin "2") (pinfunction "VINA-_2") (pintype "input"))
    )
    (net (code "83") (name "Net-(U6-IN)") (class "Default")
      (node (ref "C29") (pin "2") (pinfunction "2_2") (pintype "input"))
      (node (ref "H5") (pin "2") (pinfunction "2_2") (pintype "input"))
      (node (ref "U6") (pin "8") (pinfunction "IN_8") (pintype "unspecified"))
    )
    (net (code "84") (name "Net-(U6-OUT)") (class "Default")
      (node (ref "H5") (pin "1") (pinfunction "1_1") (pintype "input"))
      (node (ref "R43") (pin "2") (pinfunction "2_2") (pintype "input"))
      (node (ref "U6") (pin "2") (pinfunction "OUT_2") (pintype "output"))
      (node (ref "U7") (pin "3") (pinfunction "VIN+_3") (pintype "input"))
    )
    (net (code "85") (name "Net-(U6-VREFIN)") (class "Default")
      (node (ref "C58") (pin "1") (pinfunction "1_1") (pintype "input"))
      (node (ref "R41") (pin "2") (pinfunction "2_2") (pintype "input"))
      (node (ref "U6") (pin "1") (pinfunction "VREFIN_1") (pintype "unspecified"))
    )
    (net (code "86") (name "Net-(U7-VIN-)") (class "Default")
      (node (ref "R51") (pin "3") (pinfunction "3_3") (pintype "input"))
      (node (ref "U7") (pin "1") (pinfunction "VOUT_1") (pintype "output"))
      (node (ref "U7") (pin "4") (pinfunction "VIN-_4") (pintype "input"))
    )
    (net (code "87") (name "Net-(U9A-VINB-)") (class "Default")
      (node (ref "C57") (pin "1") (pinfunction "1_1") (pintype "input"))
      (node (ref "R86") (pin "2") (pinfunction "2_2") (pintype "input"))
      (node (ref "R87") (pin "1") (pinfunction "1_1") (pintype "input"))
      (node (ref "U9") (pin "6") (pinfunction "VINB-_6") (pintype "input"))
    )
    (net (code "88") (name "Net-(U9A-VOUTB)") (class "Default")
      (node (ref "C41") (pin "1") (pinfunction "1_1") (pintype "input"))
      (node (ref "C57") (pin "2") (pinfunction "2_2") (pintype "input"))
      (node (ref "R59") (pin "1") (pinfunction "1_1") (pintype "input"))
      (node (ref "R87") (pin "2") (pinfunction "2_2") (pintype "input"))
      (node (ref "U9") (pin "7") (pinfunction "VOUTB_7") (pintype "output"))
    )
    (net (code "89") (name "Net-(U9B-VINA+)") (class "Default")
      (node (ref "R77") (pin "2") (pinfunction "2_2") (pintype "input"))
      (node (ref "U9") (pin "3") (pinfunction "VINA+_3") (pintype "input"))
    )
    (net (code "90") (name "Net-(U9B-VINA-)") (class "Default")
      (node (ref "C54") (pin "1") (pinfunction "1_1") (pintype "input"))
      (node (ref "R53") (pin "2") (pinfunction "2_2") (pintype "input"))
      (node (ref "R54") (pin "2") (pinfunction "2_2") (pintype "input"))
      (node (ref "R57") (pin "1") (pinfunction "1_1") (pintype "input"))
      (node (ref "U9") (pin "2") (pinfunction "VINA-_2") (pintype "input"))
    )
    (net (code "91") (name "Net-(U9B-VOUTA)") (class "Default")
      (node (ref "C40") (pin "1") (pinfunction "1_1") (pintype "input"))
      (node (ref "C54") (pin "2") (pinfunction "2_2") (pintype "input"))
      (node (ref "R57") (pin "2") (pinfunction "2_2") (pintype "input"))
      (node (ref "R58") (pin "1") (pinfunction "1_1") (pintype "input"))
      (node (ref "U9") (pin "1") (pinfunction "VOUTA_1") (pintype "output"))
    )
    (net (code "92") (name "Net-(U10A-VINB+)") (class "Default")
      (node (ref "R55") (pin "2") (pinfunction "2_2") (pintype "input"))
      (node (ref "U10") (pin "3") (pinfunction "VINA+_3") (pintype "input"))
      (node (ref "U10") (pin "5") (pinfunction "VINB+_5") (pintype "input"))
    )
    (net (code "93") (name "Net-(U10A-VINB-)") (class "Default")
      (node (ref "C56") (pin "2") (pinfunction "2_2") (pintype "input"))
      (node (ref "R65") (pin "1") (pinfunction "1_1") (pintype "input"))
      (node (ref "R66") (pin "2") (pinfunction "2_2") (pintype "input"))
      (node (ref "U10") (pin "6") (pinfunction "VINB-_6") (pintype "input"))
    )
    (net (code "94") (name "Net-(U10A-VOUTB)") (class "Default")
      (node (ref "C44") (pin "1") (pinfunction "1_1") (pintype "input"))
      (node (ref "C56") (pin "1") (pinfunction "1_1") (pintype "input"))
      (node (ref "R66") (pin "1") (pinfunction "1_1") (pintype "input"))
      (node (ref "U10") (pin "7") (pinfunction "VOUTB_7") (pintype "output"))
    )
    (net (code "95") (name "Net-(U10B-VINA-)") (class "Default")
      (node (ref "C55") (pin "1") (pinfunction "1_1") (pintype "input"))
      (node (ref "R64") (pin "1") (pinfunction "1_1") (pintype "input"))
      (node (ref "R85") (pin "1") (pinfunction "1_1") (pintype "input"))
      (node (ref "U10") (pin "2") (pinfunction "VINA-_2") (pintype "input"))
    )
    (net (code "96") (name "Net-(U12-P3.5{slash}ADC13{slash}T1)") (class "Default")
      (node (ref "R73") (pin "2") (pinfunction "2_2") (pintype "input"))
      (node (ref "U12") (pin "13") (pinfunction "P3.5/ADC13/T1_13") (pintype "unspecified"))
    )
    (net (code "97") (name "Net-(U12-P3.6{slash}ADC14{slash}INT2)") (class "Default")
      (node (ref "R91") (pin "2") (pinfunction "2_2") (pintype "input"))
      (node (ref "U12") (pin "14") (pinfunction "P3.6/ADC14/INT2_14") (pintype "unspecified"))
    )
    (net (code "98") (name "Net-(U12-P3.7{slash}INT3{slash}TXD_2)") (class "Default")
      (node (ref "R92") (pin "2") (pinfunction "2_2") (pintype "input"))
      (node (ref "U12") (pin "15") (pinfunction "P3.7/INT3/TXD_2_15") (pintype "unspecified"))
    )
    (net (code "99") (name "Net-(U12-XTALI{slash}ADC7{slash}P1.7)") (class "Default")
      (node (ref "R104") (pin "1") (pinfunction "1_1") (pintype "input"))
      (node (ref "U12") (pin "3") (pinfunction "XTALI/ADC7/P1.7_3") (pintype "unspecified"))
    )
    (net (code "100") (name "OUTMON") (class "Default")
      (node (ref "C43") (pin "1") (pinfunction "1_1") (pintype "input"))
      (node (ref "C55") (pin "2") (pinfunction "2_2") (pintype "input"))
      (node (ref "R64") (pin "2") (pinfunction "2_2") (pintype "input"))
      (node (ref "R65") (pin "2") (pinfunction "2_2") (pintype "input"))
      (node (ref "U10") (pin "1") (pinfunction "VOUTA_1") (pintype "output"))
      (node (ref "U12") (pin "17") (pinfunction "12CSDA/MISO/ADC4/P1.4_17") (pintype "unspecified"))
    )
    (net (code "101") (name "RST{slash}P5.4") (class "Default")
      (node (ref "R100") (pin "1") (pinfunction "1_1") (pintype "input"))
      (node (ref "R101") (pin "1") (pinfunction "1_1") (pintype "input"))
      (node (ref "U12") (pin "4") (pinfunction "MCLKO/RST/P5.4_4") (pintype "unspecified"))
    )
    (net (code "102") (name "RXD{slash}P3.0") (class "Default")
      (node (ref "D9") (pin "2") (pinfunction "A_2") (pintype "input"))
      (node (ref "U12") (pin "8") (pinfunction "P3.0/ADC8/RXD/INT4_8") (pintype "unspecified"))
    )
    (net (code "103") (name "SCL") (class "Default")
      (node (ref "CN14") (pin "4") (pinfunction "4_4") (pintype "unspecified"))
      (node (ref "R102") (pin "1") (pinfunction "1_1") (pintype "input"))
      (node (ref "U12") (pin "20") (pinfunction "CCP0/TXD2/ADC1/P1.1_20") (pintype "unspecified"))
    )
    (net (code "104") (name "SDA") (class "Default")
      (node (ref "CN14") (pin "3") (pinfunction "3_3") (pintype "unspecified"))
      (node (ref "R103") (pin "1") (pinfunction "1_1") (pintype "input"))
      (node (ref "U12") (pin "19") (pinfunction "T2/ECI/SS/ADC2/P1.2_19") (pintype "unspecified"))
    )
    (net (code "105") (name "SWITCH1") (class "Default")
      (node (ref "SW1") (pin "1") (pinfunction "1_1") (pintype "unspecified"))
      (node (ref "U12") (pin "1") (pinfunction "SCLK/ADC5/P1.5_1") (pintype "unspecified"))
    )
    (net (code "106") (name "SWITCH2") (class "Default")
      (node (ref "SW2") (pin "1") (pinfunction "1_1") (pintype "unspecified"))
      (node (ref "U12") (pin "2") (pinfunction "XTALO/ADC6/P1.6_2") (pintype "unspecified"))
    )
    (net (code "107") (name "TP1") (class "Default")
      (node (ref "H6") (pin "2") (pinfunction "2_2") (pintype "input"))
      (node (ref "U12") (pin "18") (pinfunction "T2CLKO/MOSI/ADC3/P1.3_18") (pintype "unspecified"))
    )
    (net (code "108") (name "TXD{slash}P3.1") (class "Default")
      (node (ref "R99") (pin "1") (pinfunction "1_1") (pintype "input"))
      (node (ref "U12") (pin "9") (pinfunction "P3.1/ADC9/TXD_9") (pintype "unspecified"))
    )
    (net (code "109") (name "VOICEOUT") (class "Default")
      (node (ref "CN5") (pin "1") (pinfunction "1_1") (pintype "input"))
      (node (ref "R63") (pin "2") (pinfunction "2_2") (pintype "input"))
    )
    (net (code "110") (name "VOL_ADC1") (class "Default")
      (node (ref "C51") (pin "2") (pinfunction "2_2") (pintype "input"))
      (node (ref "C61") (pin "2") (pinfunction "2_2") (pintype "input"))
      (node (ref "CN3") (pin "3") (pinfunction "3_3") (pintype "input"))
      (node (ref "R104") (pin "2") (pinfunction "2_2") (pintype "input"))
      (node (ref "R74") (pin "1") (pinfunction "1_1") (pintype "input"))
    )
    (net (code "111") (name "VOL_CLK") (class "Default")
      (node (ref "U12") (pin "10") (pinfunction "P3.2/ADC10/INTO_10") (pintype "unspecified"))
      (node (ref "U6") (pin "6") (pinfunction "CLOCK_6") (pintype "unspecified"))
    )
    (net (code "112") (name "VOL_DATA") (class "Default")
      (node (ref "U12") (pin "11") (pinfunction "P3.3/ADC11/INT1_11") (pintype "unspecified"))
      (node (ref "U6") (pin "5") (pinfunction "DATA_5") (pintype "unspecified"))
    )
    (net (code "113") (name "VOL_LOAD") (class "Default")
      (node (ref "U12") (pin "12") (pinfunction "P3.4/ADC12/T0_12") (pintype "unspecified"))
      (node (ref "U6") (pin "4") (pinfunction "LOAD_4") (pintype "unspecified"))
    )
    (net (code "114") (name "Vbatt") (class "Default")
      (node (ref "C45") (pin "1") (pinfunction "1_1") (pintype "input"))
      (node (ref "C46") (pin "2") (pinfunction "2_2") (pintype "input"))
      (node (ref "CN13") (pin "1") (pinfunction "1_1") (pintype "unspecified"))
      (node (ref "R75") (pin "1") (pinfunction "1_1") (pintype "input"))
      (node (ref "U8") (pin "2") (pinfunction "VIN_2") (pintype "input"))
    )
    (net (code "115") (name "Vgnd") (class "Default")
      (node (ref "C16") (pin "2") (pinfunction "2_2") (pintype "input"))
      (node (ref "C4") (pin "2") (pinfunction "2_2") (pintype "input"))
      (node (ref "C49") (pin "1") (pinfunction "1_1") (pintype "input"))
      (node (ref "C50") (pin "2") (pinfunction "2_2") (pintype "input"))
      (node (ref "R12") (pin "2") (pinfunction "2_2") (pintype "input"))
      (node (ref "R21") (pin "2") (pinfunction "2_2") (pintype "input"))
      (node (ref "R23") (pin "1") (pinfunction "1_1") (pintype "input"))
      (node (ref "R24") (pin "2") (pinfunction "2_2") (pintype "input"))
      (node (ref "R25") (pin "1") (pinfunction "1_1") (pintype "input"))
      (node (ref "R28") (pin "2") (pinfunction "2_2") (pintype "input"))
      (node (ref "R39") (pin "2") (pinfunction "2_2") (pintype "input"))
      (node (ref "R41") (pin "1") (pinfunction "1_1") (pintype "input"))
      (node (ref "R43") (pin "1") (pinfunction "1_1") (pintype "input"))
      (node (ref "R5") (pin "2") (pinfunction "2_2") (pintype "input"))
      (node (ref "R50") (pin "2") (pinfunction "2_2") (pintype "input"))
      (node (ref "R51") (pin "1") (pinfunction "1_1") (pintype "input"))
      (node (ref "R52") (pin "1") (pinfunction "1_1") (pintype "input"))
      (node (ref "R55") (pin "1") (pinfunction "1_1") (pintype "input"))
      (node (ref "R56") (pin "2") (pinfunction "2_2") (pintype "input"))
      (node (ref "R7") (pin "1") (pinfunction "1_1") (pintype "input"))
      (node (ref "R71") (pin "2") (pinfunction "2_2") (pintype "input"))
      (node (ref "R72") (pin "1") (pinfunction "1_1") (pintype "input"))
      (node (ref "R77") (pin "1") (pinfunction "1_1") (pintype "input"))
      (node (ref "R8") (pin "2") (pinfunction "2_2") (pintype "input"))
      (node (ref "R86") (pin "1") (pinfunction "1_1") (pintype "input"))
      (node (ref "R9") (pin "1") (pinfunction "1_1") (pintype "input"))
    )
    (net (code "116") (name "unconnected-(U12-EP-Pad21)") (class "Default")
      (node (ref "U12") (pin "21") (pinfunction "EP_21") (pintype "unspecified+no_connect"))
    )
    (net (code "117") (name "unconnected-(U12-P5.5-Pad6)") (class "Default")
      (node (ref "U12") (pin "6") (pinfunction "P5.5_6") (pintype "unspecified+no_connect"))
    )
  )
)
